# STM32F446_front_pane_-_northeast_-_v3.net
KiCad netlist of a schematic drawn in EAGLE
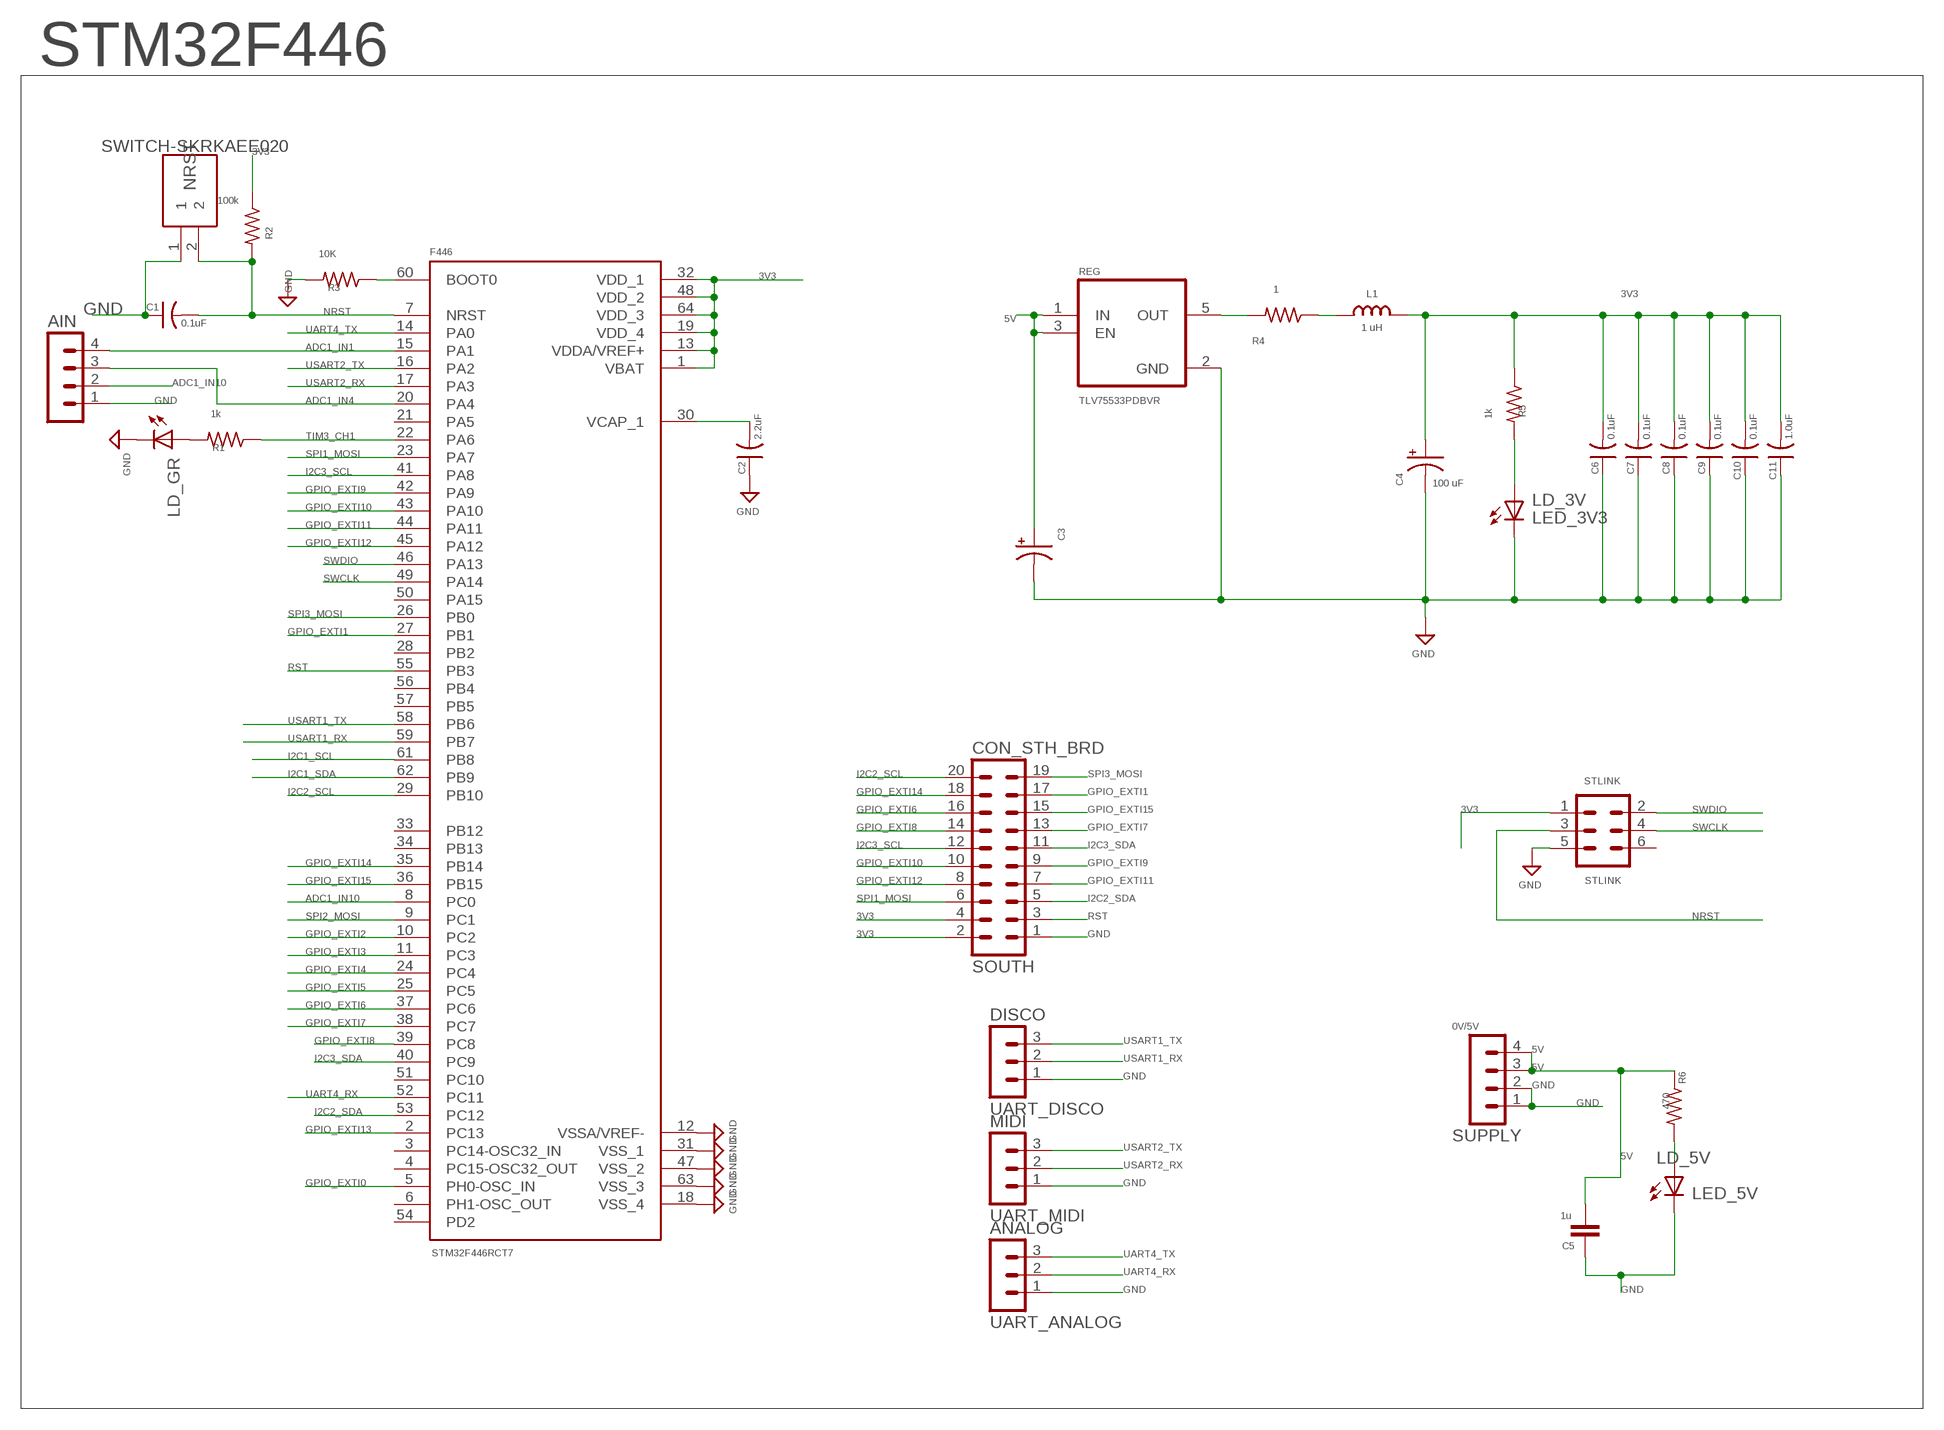
[diagram p0: schematic, sheet 1]
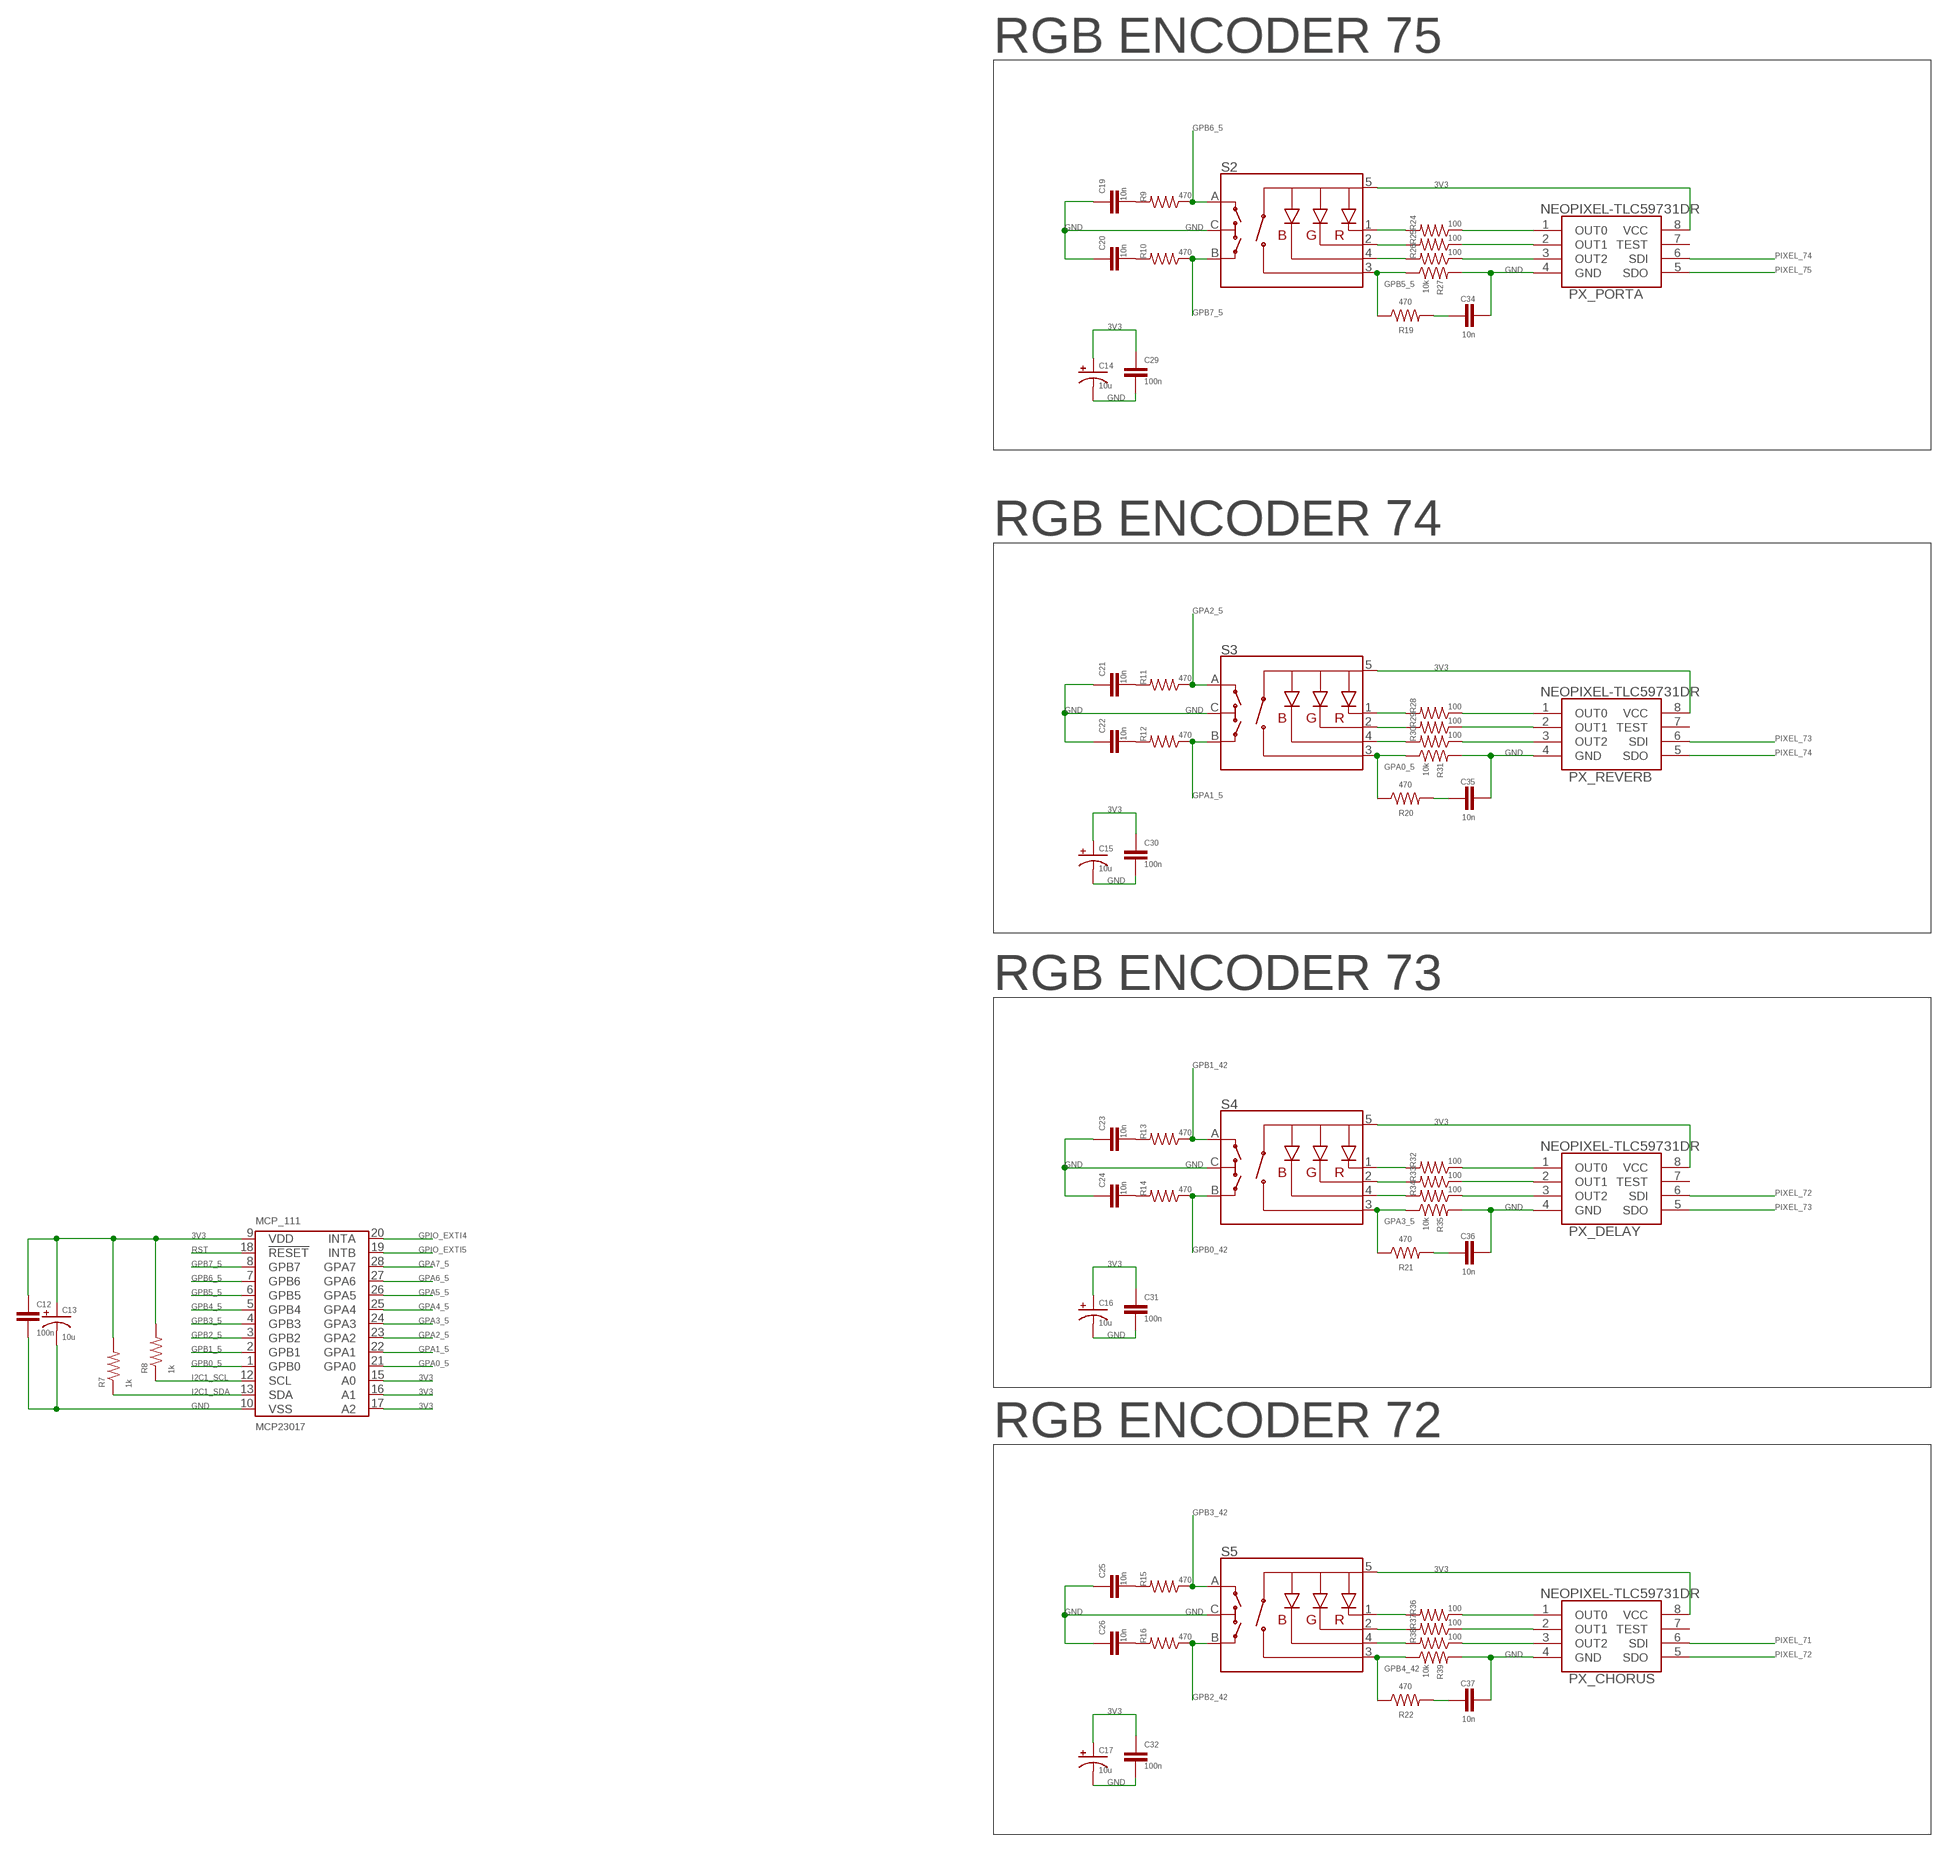
[diagram p1: schematic, sheet 2, part 1 of 2]
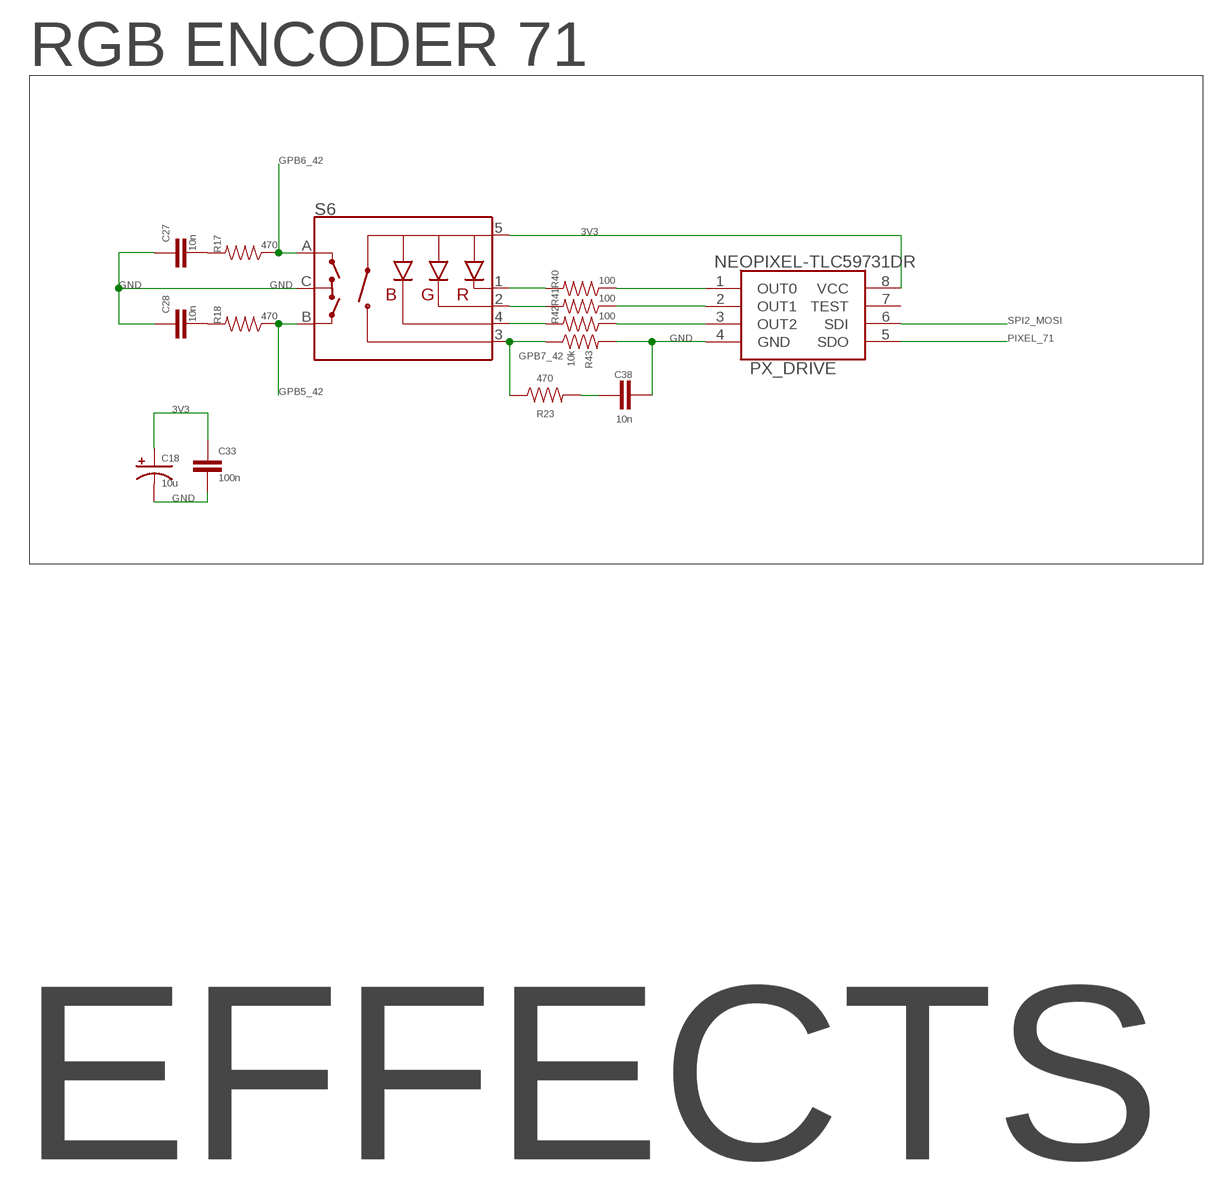
[diagram p2: schematic, sheet 2, part 2 of 2]
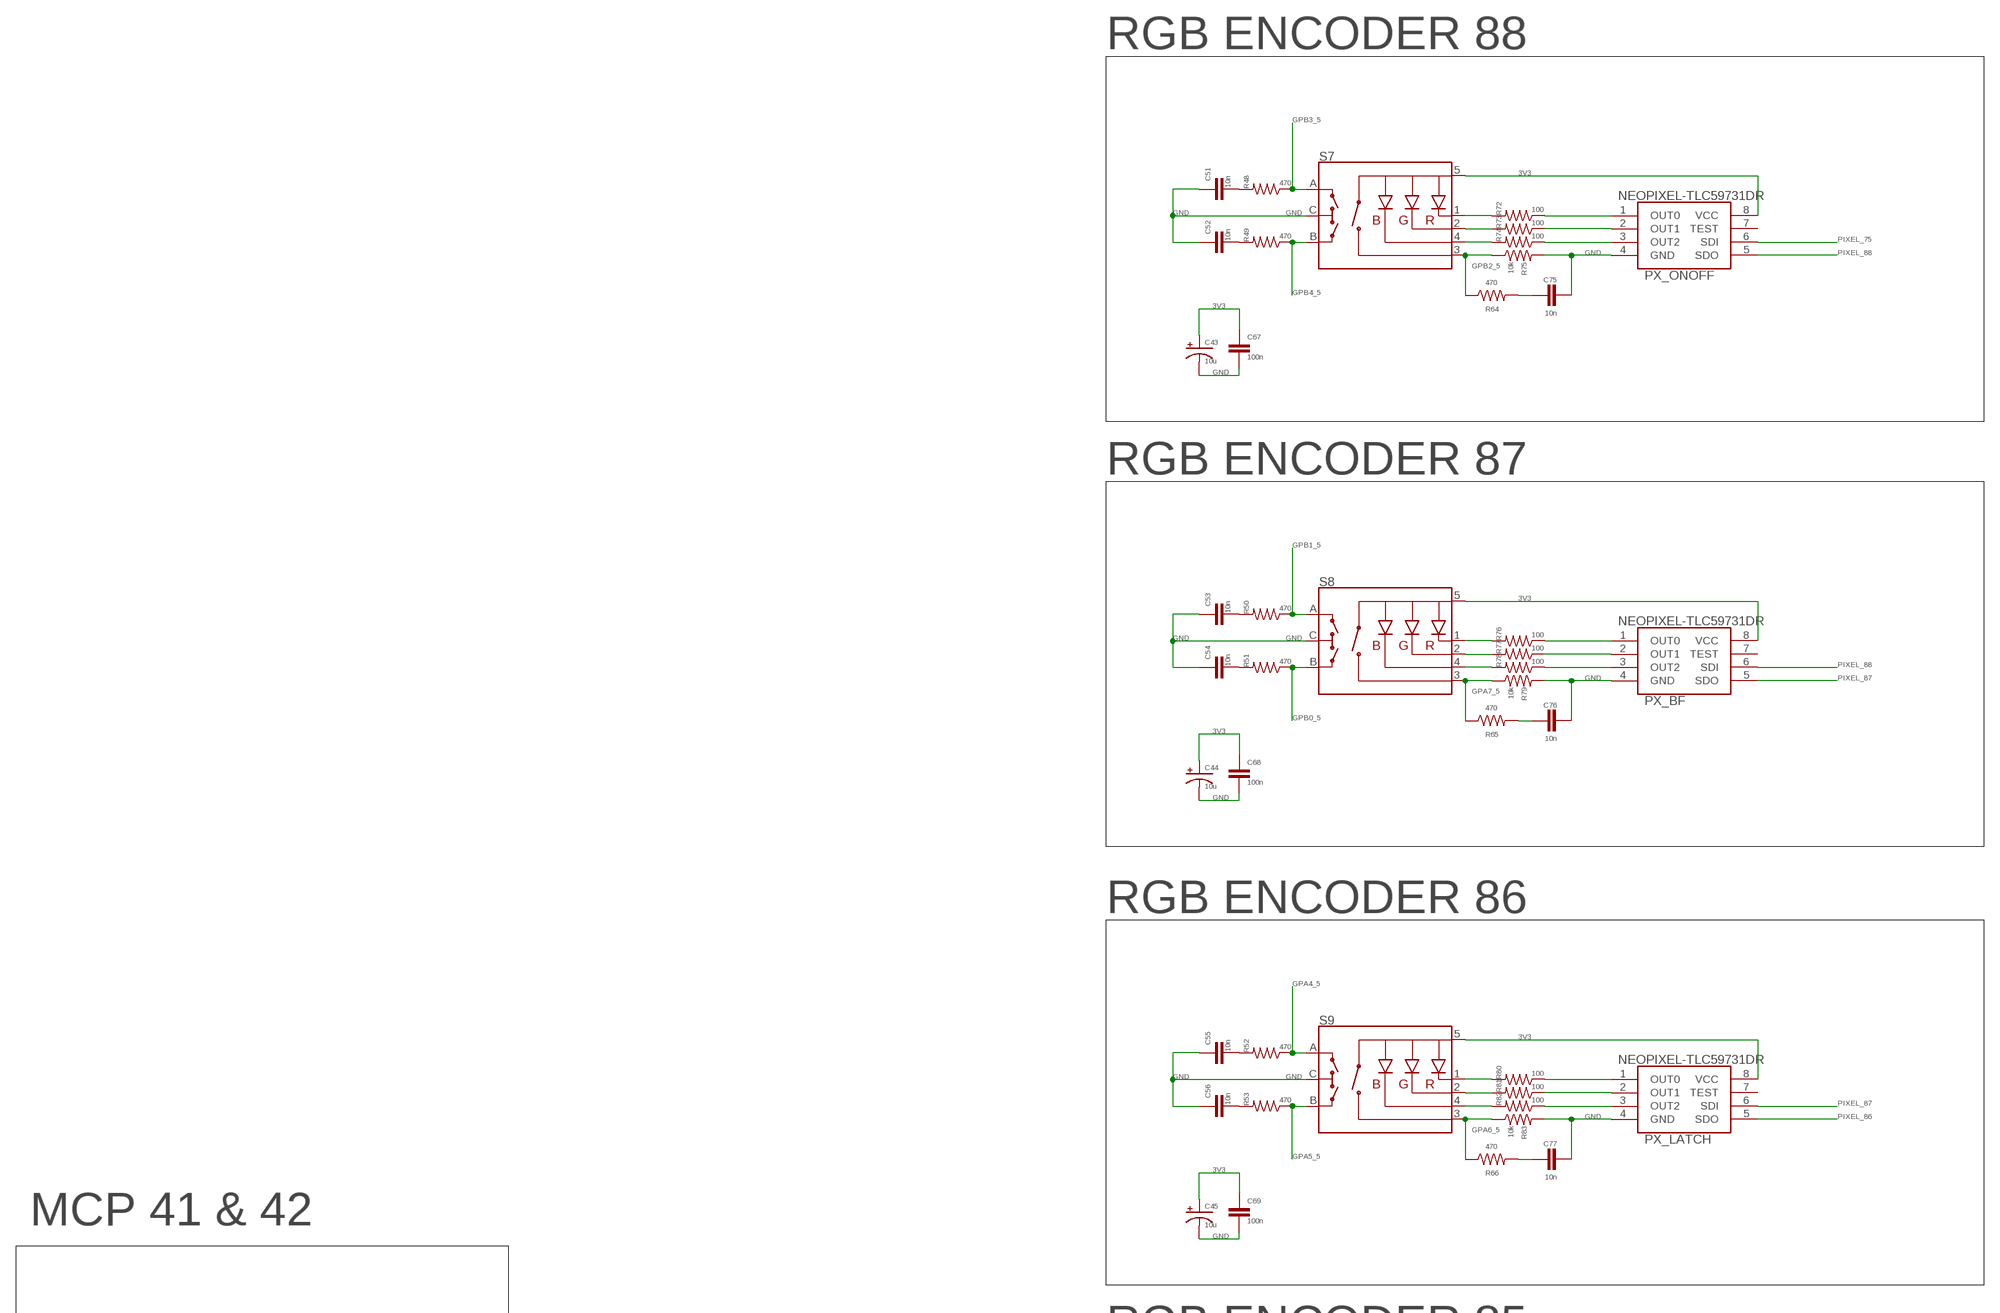
[diagram p3: schematic, sheet 3, part 1 of 2]
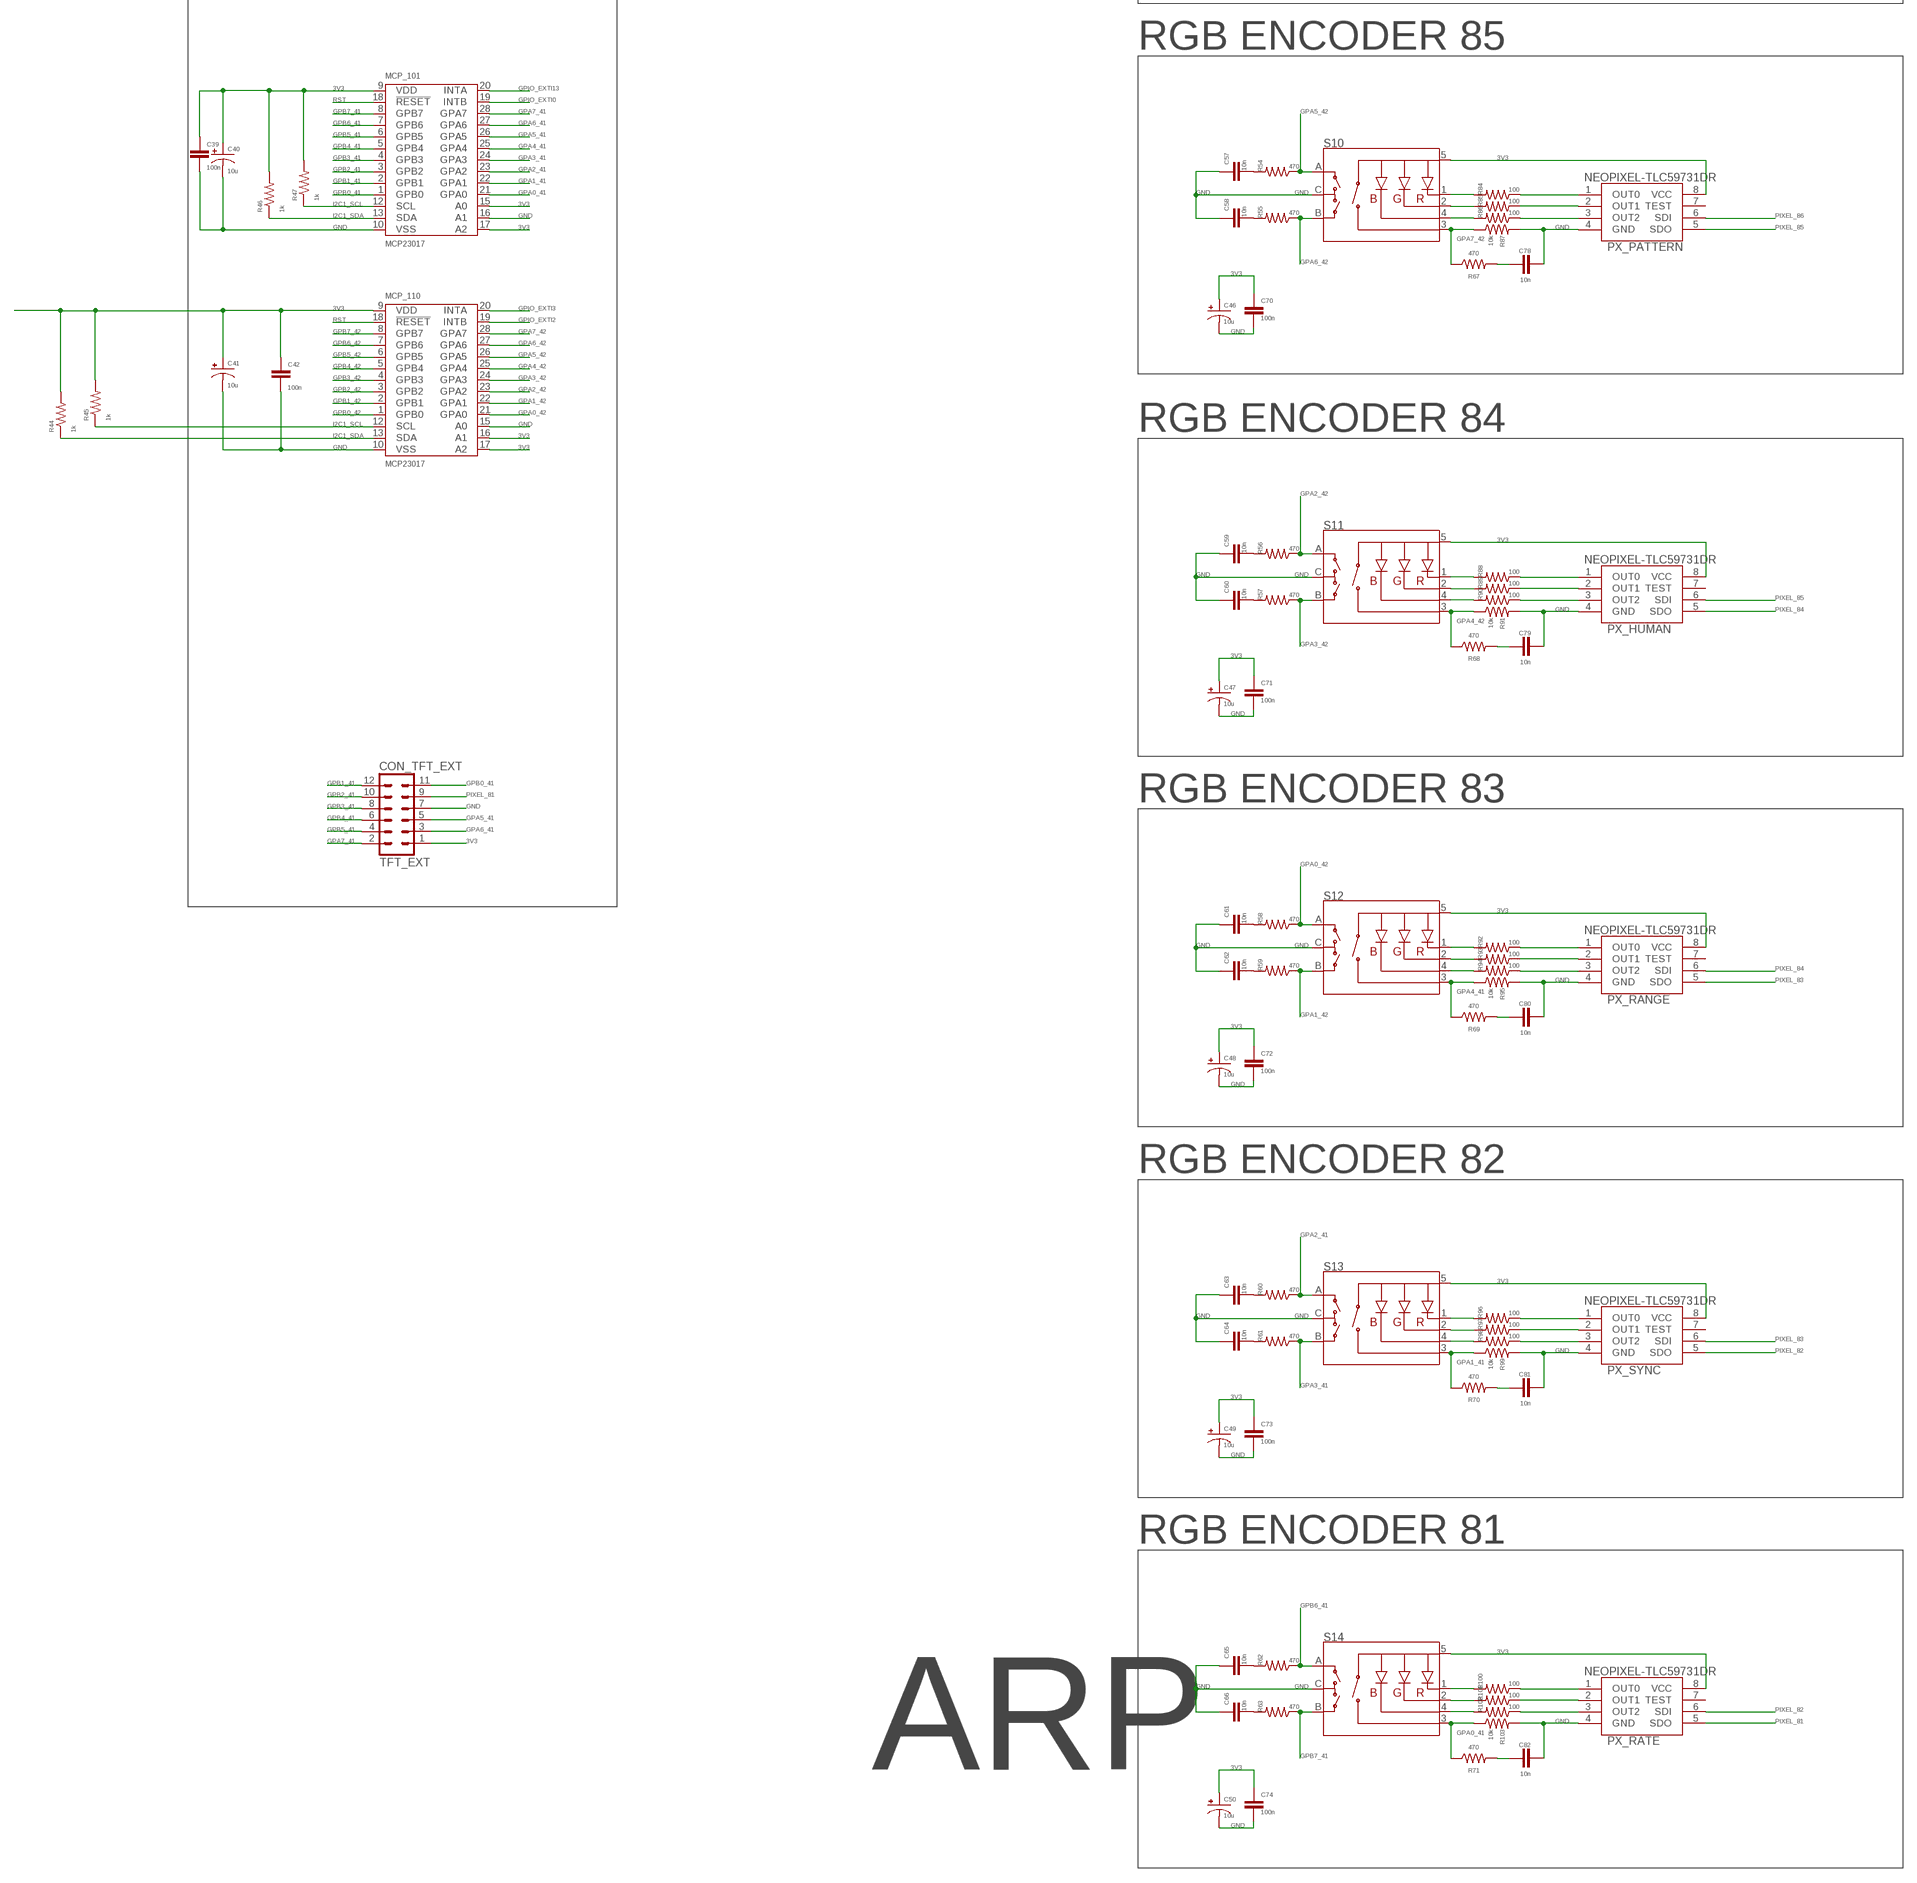
[diagram p4: schematic, sheet 3, part 2 of 2]

(export (version "E")
  (design (tool "Eeschema 10.0.6"))
  (components
    (comp (ref "C12")
      (value "100n")
      (footprint "eagle-import:0805-CAP")
      (libsource (lib "eagle-import") (part "PASSIF-CAP-0805"))
    )
    (comp (ref "C13")
      (value "10u")
      (footprint "eagle-import:CPOL2917")
      (libsource (lib "eagle-import") (part "PASSIF-CPOL-US2917"))
    )
    (comp (ref "C14")
      (value "10u")
      (footprint "eagle-import:CPOL2917")
      (libsource (lib "eagle-import") (part "PASSIF-CPOL-US2917"))
    )
    (comp (ref "C15")
      (value "10u")
      (footprint "eagle-import:CPOL2917")
      (libsource (lib "eagle-import") (part "PASSIF-CPOL-US2917"))
    )
    (comp (ref "C16")
      (value "10u")
      (footprint "eagle-import:CPOL2917")
      (libsource (lib "eagle-import") (part "PASSIF-CPOL-US2917"))
    )
    (comp (ref "C17")
      (value "10u")
      (footprint "eagle-import:CPOL2917")
      (libsource (lib "eagle-import") (part "PASSIF-CPOL-US2917"))
    )
    (comp (ref "C18")
      (value "10u")
      (footprint "eagle-import:CPOL2917")
      (libsource (lib "eagle-import") (part "PASSIF-CPOL-US2917"))
    )
    (comp (ref "C19")
      (value "10n")
      (footprint "eagle-import:0805-CAP")
      (libsource (lib "eagle-import") (part "PASSIF-CAP-0805"))
    )
    (comp (ref "C20")
      (value "10n")
      (footprint "eagle-import:0805-CAP")
      (libsource (lib "eagle-import") (part "PASSIF-CAP-0805"))
    )
    (comp (ref "C21")
      (value "10n")
      (footprint "eagle-import:0805-CAP")
      (libsource (lib "eagle-import") (part "PASSIF-CAP-0805"))
    )
    (comp (ref "C22")
      (value "10n")
      (footprint "eagle-import:0805-CAP")
      (libsource (lib "eagle-import") (part "PASSIF-CAP-0805"))
    )
    (comp (ref "C23")
      (value "10n")
      (footprint "eagle-import:0805-CAP")
      (libsource (lib "eagle-import") (part "PASSIF-CAP-0805"))
    )
    (comp (ref "C24")
      (value "10n")
      (footprint "eagle-import:0805-CAP")
      (libsource (lib "eagle-import") (part "PASSIF-CAP-0805"))
    )
    (comp (ref "C25")
      (value "10n")
      (footprint "eagle-import:0805-CAP")
      (libsource (lib "eagle-import") (part "PASSIF-CAP-0805"))
    )
    (comp (ref "C26")
      (value "10n")
      (footprint "eagle-import:0805-CAP")
      (libsource (lib "eagle-import") (part "PASSIF-CAP-0805"))
    )
    (comp (ref "C27")
      (value "10n")
      (footprint "eagle-import:0805-CAP")
      (libsource (lib "eagle-import") (part "PASSIF-CAP-0805"))
    )
    (comp (ref "C28")
      (value "10n")
      (footprint "eagle-import:0805-CAP")
      (libsource (lib "eagle-import") (part "PASSIF-CAP-0805"))
    )
    (comp (ref "C29")
      (value "100n")
      (footprint "eagle-import:0805-CAP")
      (libsource (lib "eagle-import") (part "PASSIF-CAP-0805"))
    )
    (comp (ref "C30")
      (value "100n")
      (footprint "eagle-import:0805-CAP")
      (libsource (lib "eagle-import") (part "PASSIF-CAP-0805"))
    )
    (comp (ref "C31")
      (value "100n")
      (footprint "eagle-import:0805-CAP")
      (libsource (lib "eagle-import") (part "PASSIF-CAP-0805"))
    )
    (comp (ref "C32")
      (value "100n")
      (footprint "eagle-import:0805-CAP")
      (libsource (lib "eagle-import") (part "PASSIF-CAP-0805"))
    )
    (comp (ref "C33")
      (value "100n")
      (footprint "eagle-import:0805-CAP")
      (libsource (lib "eagle-import") (part "PASSIF-CAP-0805"))
    )
    (comp (ref "C34")
      (value "10n")
      (footprint "eagle-import:0805-CAP")
      (libsource (lib "eagle-import") (part "PASSIF-CAP-0805"))
    )
    (comp (ref "C35")
      (value "10n")
      (footprint "eagle-import:0805-CAP")
      (libsource (lib "eagle-import") (part "PASSIF-CAP-0805"))
    )
    (comp (ref "C36")
      (value "10n")
      (footprint "eagle-import:0805-CAP")
      (libsource (lib "eagle-import") (part "PASSIF-CAP-0805"))
    )
    (comp (ref "C37")
      (value "10n")
      (footprint "eagle-import:0805-CAP")
      (libsource (lib "eagle-import") (part "PASSIF-CAP-0805"))
    )
    (comp (ref "C38")
      (value "10n")
      (footprint "eagle-import:0805-CAP")
      (libsource (lib "eagle-import") (part "PASSIF-CAP-0805"))
    )
    (comp (ref "MCP_111")
      (value "MCP23017")
      (footprint "eagle-import:SOIC-28")
      (libsource (lib "eagle-import") (part "MCP23017"))
    )
    (comp (ref "PX_CHORUS")
      (value "NEOPIXEL-TLC59731DR")
      (footprint "eagle-import:SOIC127P600X175-8N")
      (fields
        (field (name "ARROW_PART_NUMBER") "TLC59731DR")
        (field (name "MOUSER_PART_NUMBER") "595-TLC59731DR")
      )
      (libsource (lib "eagle-import") (part "NEOPIXEL-TLC59731DR"))
    )
    (comp (ref "PX_DELAY")
      (value "NEOPIXEL-TLC59731DR")
      (footprint "eagle-import:SOIC127P600X175-8N")
      (fields
        (field (name "ARROW_PART_NUMBER") "TLC59731DR")
        (field (name "MOUSER_PART_NUMBER") "595-TLC59731DR")
      )
      (libsource (lib "eagle-import") (part "NEOPIXEL-TLC59731DR"))
    )
    (comp (ref "PX_DRIVE")
      (value "NEOPIXEL-TLC59731DR")
      (footprint "eagle-import:SOIC127P600X175-8N")
      (fields
        (field (name "ARROW_PART_NUMBER") "TLC59731DR")
        (field (name "MOUSER_PART_NUMBER") "595-TLC59731DR")
      )
      (libsource (lib "eagle-import") (part "NEOPIXEL-TLC59731DR"))
    )
    (comp (ref "PX_PORTA")
      (value "NEOPIXEL-TLC59731DR")
      (footprint "eagle-import:SOIC127P600X175-8N")
      (fields
        (field (name "ARROW_PART_NUMBER") "TLC59731DR")
        (field (name "MOUSER_PART_NUMBER") "595-TLC59731DR")
      )
      (libsource (lib "eagle-import") (part "NEOPIXEL-TLC59731DR"))
    )
    (comp (ref "PX_REVERB")
      (value "NEOPIXEL-TLC59731DR")
      (footprint "eagle-import:SOIC127P600X175-8N")
      (fields
        (field (name "ARROW_PART_NUMBER") "TLC59731DR")
        (field (name "MOUSER_PART_NUMBER") "595-TLC59731DR")
      )
      (libsource (lib "eagle-import") (part "NEOPIXEL-TLC59731DR"))
    )
    (comp (ref "R7")
      (value "1k")
      (footprint "eagle-import:R0805")
      (libsource (lib "eagle-import") (part "R-US_R0805"))
    )
    (comp (ref "R8")
      (value "1k")
      (footprint "eagle-import:R0805")
      (libsource (lib "eagle-import") (part "R-US_R0805"))
    )
    (comp (ref "R9")
      (value "470")
      (footprint "eagle-import:1206")
      (libsource (lib "eagle-import") (part "PASSIF-RESISTOR-1206"))
    )
    (comp (ref "R10")
      (value "470")
      (footprint "eagle-import:1206")
      (libsource (lib "eagle-import") (part "PASSIF-RESISTOR-1206"))
    )
    (comp (ref "R11")
      (value "470")
      (footprint "eagle-import:1206")
      (libsource (lib "eagle-import") (part "PASSIF-RESISTOR-1206"))
    )
    (comp (ref "R12")
      (value "470")
      (footprint "eagle-import:1206")
      (libsource (lib "eagle-import") (part "PASSIF-RESISTOR-1206"))
    )
    (comp (ref "R13")
      (value "470")
      (footprint "eagle-import:1206")
      (libsource (lib "eagle-import") (part "PASSIF-RESISTOR-1206"))
    )
    (comp (ref "R14")
      (value "470")
      (footprint "eagle-import:1206")
      (libsource (lib "eagle-import") (part "PASSIF-RESISTOR-1206"))
    )
    (comp (ref "R15")
      (value "470")
      (footprint "eagle-import:1206")
      (libsource (lib "eagle-import") (part "PASSIF-RESISTOR-1206"))
    )
    (comp (ref "R16")
      (value "470")
      (footprint "eagle-import:1206")
      (libsource (lib "eagle-import") (part "PASSIF-RESISTOR-1206"))
    )
    (comp (ref "R17")
      (value "470")
      (footprint "eagle-import:1206")
      (libsource (lib "eagle-import") (part "PASSIF-RESISTOR-1206"))
    )
    (comp (ref "R18")
      (value "470")
      (footprint "eagle-import:1206")
      (libsource (lib "eagle-import") (part "PASSIF-RESISTOR-1206"))
    )
    (comp (ref "R19")
      (value "470")
      (footprint "eagle-import:1206")
      (libsource (lib "eagle-import") (part "PASSIF-RESISTOR-1206"))
    )
    (comp (ref "R20")
      (value "470")
      (footprint "eagle-import:1206")
      (libsource (lib "eagle-import") (part "PASSIF-RESISTOR-1206"))
    )
    (comp (ref "R21")
      (value "470")
      (footprint "eagle-import:1206")
      (libsource (lib "eagle-import") (part "PASSIF-RESISTOR-1206"))
    )
    (comp (ref "R22")
      (value "470")
      (footprint "eagle-import:1206")
      (libsource (lib "eagle-import") (part "PASSIF-RESISTOR-1206"))
    )
    (comp (ref "R23")
      (value "470")
      (footprint "eagle-import:1206")
      (libsource (lib "eagle-import") (part "PASSIF-RESISTOR-1206"))
    )
    (comp (ref "R24")
      (value "100")
      (footprint "eagle-import:1206")
      (libsource (lib "eagle-import") (part "PASSIF-RESISTOR-1206"))
    )
    (comp (ref "R25")
      (value "100")
      (footprint "eagle-import:1206")
      (libsource (lib "eagle-import") (part "PASSIF-RESISTOR-1206"))
    )
    (comp (ref "R26")
      (value "100")
      (footprint "eagle-import:1206")
      (libsource (lib "eagle-import") (part "PASSIF-RESISTOR-1206"))
    )
    (comp (ref "R27")
      (value "10k")
      (footprint "eagle-import:1206")
      (libsource (lib "eagle-import") (part "PASSIF-RESISTOR-1206"))
    )
    (comp (ref "R28")
      (value "100")
      (footprint "eagle-import:1206")
      (libsource (lib "eagle-import") (part "PASSIF-RESISTOR-1206"))
    )
    (comp (ref "R29")
      (value "100")
      (footprint "eagle-import:1206")
      (libsource (lib "eagle-import") (part "PASSIF-RESISTOR-1206"))
    )
    (comp (ref "R30")
      (value "100")
      (footprint "eagle-import:1206")
      (libsource (lib "eagle-import") (part "PASSIF-RESISTOR-1206"))
    )
    (comp (ref "R31")
      (value "10k")
      (footprint "eagle-import:1206")
      (libsource (lib "eagle-import") (part "PASSIF-RESISTOR-1206"))
    )
    (comp (ref "R32")
      (value "100")
      (footprint "eagle-import:1206")
      (libsource (lib "eagle-import") (part "PASSIF-RESISTOR-1206"))
    )
    (comp (ref "R33")
      (value "100")
      (footprint "eagle-import:1206")
      (libsource (lib "eagle-import") (part "PASSIF-RESISTOR-1206"))
    )
    (comp (ref "R34")
      (value "100")
      (footprint "eagle-import:1206")
      (libsource (lib "eagle-import") (part "PASSIF-RESISTOR-1206"))
    )
    (comp (ref "R35")
      (value "10k")
      (footprint "eagle-import:1206")
      (libsource (lib "eagle-import") (part "PASSIF-RESISTOR-1206"))
    )
    (comp (ref "R36")
      (value "100")
      (footprint "eagle-import:1206")
      (libsource (lib "eagle-import") (part "PASSIF-RESISTOR-1206"))
    )
    (comp (ref "R37")
      (value "100")
      (footprint "eagle-import:1206")
      (libsource (lib "eagle-import") (part "PASSIF-RESISTOR-1206"))
    )
    (comp (ref "R38")
      (value "100")
      (footprint "eagle-import:1206")
      (libsource (lib "eagle-import") (part "PASSIF-RESISTOR-1206"))
    )
    (comp (ref "R39")
      (value "10k")
      (footprint "eagle-import:1206")
      (libsource (lib "eagle-import") (part "PASSIF-RESISTOR-1206"))
    )
    (comp (ref "R40")
      (value "100")
      (footprint "eagle-import:1206")
      (libsource (lib "eagle-import") (part "PASSIF-RESISTOR-1206"))
    )
    (comp (ref "R41")
      (value "100")
      (footprint "eagle-import:1206")
      (libsource (lib "eagle-import") (part "PASSIF-RESISTOR-1206"))
    )
    (comp (ref "R42")
      (value "100")
      (footprint "eagle-import:1206")
      (libsource (lib "eagle-import") (part "PASSIF-RESISTOR-1206"))
    )
    (comp (ref "R43")
      (value "10k")
      (footprint "eagle-import:1206")
      (libsource (lib "eagle-import") (part "PASSIF-RESISTOR-1206"))
    )
    (comp (ref "S2")
      (value "ENCODER-RGB-SWITCH-NO_NUT")
      (footprint "eagle-import:ENCODER_LED_3")
      (libsource (lib "eagle-import") (part "ENCODER-RGB-SWITCH-NO_NUT"))
    )
    (comp (ref "S3")
      (value "ENCODER-RGB-SWITCH-NO_NUT")
      (footprint "eagle-import:ENCODER_LED_3")
      (libsource (lib "eagle-import") (part "ENCODER-RGB-SWITCH-NO_NUT"))
    )
    (comp (ref "S4")
      (value "ENCODER-RGB-SWITCH-NO_NUT")
      (footprint "eagle-import:ENCODER_LED_3")
      (libsource (lib "eagle-import") (part "ENCODER-RGB-SWITCH-NO_NUT"))
    )
    (comp (ref "S5")
      (value "ENCODER-RGB-SWITCH-NO_NUT")
      (footprint "eagle-import:ENCODER_LED_3")
      (libsource (lib "eagle-import") (part "ENCODER-RGB-SWITCH-NO_NUT"))
    )
    (comp (ref "S6")
      (value "ENCODER-RGB-SWITCH-NO_NUT")
      (footprint "eagle-import:ENCODER_LED_3")
      (libsource (lib "eagle-import") (part "ENCODER-RGB-SWITCH-NO_NUT"))
    )
    (comp (ref "0V/5V")
      (value "SUPPLY")
      (footprint "eagle-import:MA04-1")
      (libsource (lib "eagle-import") (part "PINHEADER-M04PL"))
    )
    (comp (ref "AIN")
      (value "MA04-1")
      (footprint "eagle-import:MA04-1")
      (libsource (lib "eagle-import") (part "MA04-1"))
    )
    (comp (ref "ANALOG")
      (value "UART_ANALOG")
      (footprint "eagle-import:MA03-1")
      (libsource (lib "eagle-import") (part "MA03-1"))
    )
    (comp (ref "C1")
      (value "0.1uF")
      (footprint "eagle-import:C0805")
      (libsource (lib "eagle-import") (part "C-US0805"))
    )
    (comp (ref "C2")
      (value "2.2uF")
      (footprint "eagle-import:C0805")
      (libsource (lib "eagle-import") (part "C-US0805"))
    )
    (comp (ref "C3")
      (value "10u")
      (footprint "eagle-import:CPOL2917")
      (libsource (lib "eagle-import") (part "CPOL-US2917"))
    )
    (comp (ref "C4")
      (value "100 uF")
      (footprint "eagle-import:CPOL2917")
      (libsource (lib "eagle-import") (part "CPOL-US2917"))
    )
    (comp (ref "C5")
      (value "1u")
      (footprint "eagle-import:C1206")
      (libsource (lib "eagle-import") (part "C-EUC1206"))
    )
    (comp (ref "C6")
      (value "0.1uF")
      (footprint "eagle-import:C0805")
      (libsource (lib "eagle-import") (part "C-US0805"))
    )
    (comp (ref "C7")
      (value "0.1uF")
      (footprint "eagle-import:C0805")
      (libsource (lib "eagle-import") (part "C-US0805"))
    )
    (comp (ref "C8")
      (value "0.1uF")
      (footprint "eagle-import:C0805")
      (libsource (lib "eagle-import") (part "C-US0805"))
    )
    (comp (ref "C9")
      (value "0.1uF")
      (footprint "eagle-import:C0805")
      (libsource (lib "eagle-import") (part "C-US0805"))
    )
    (comp (ref "C10")
      (value "0.1uF")
      (footprint "eagle-import:C0805")
      (libsource (lib "eagle-import") (part "C-US0805"))
    )
    (comp (ref "C11")
      (value "1.0uF")
      (footprint "eagle-import:C0805")
      (libsource (lib "eagle-import") (part "C-US0805"))
    )
    (comp (ref "CON_STH_BRD")
      (value "SOUTH")
      (footprint "eagle-import:MA10-2")
      (libsource (lib "eagle-import") (part "MA10-2"))
    )
    (comp (ref "DISCO")
      (value "UART_DISCO")
      (footprint "eagle-import:MA03-1")
      (libsource (lib "eagle-import") (part "MA03-1"))
    )
    (comp (ref "F446")
      (value "STM32F446RCT7")
      (footprint "eagle-import:QFP50P1200X1200X160-64N")
      (fields (field (name "MF") "STMicroelectronics"))
      (libsource (lib "eagle-import") (part "STM32F446RCT7"))
    )
    (comp (ref "L1")
      (value "1 uH")
      (footprint "eagle-import:L0805")
      (libsource (lib "eagle-import") (part "L-USL0805"))
    )
    (comp (ref "LD_3V")
      (value "LED_3V3")
      (footprint "eagle-import:0805-LED")
      (libsource (lib "eagle-import") (part "LED-0805"))
    )
    (comp (ref "LD_5V")
      (value "LED_5V")
      (footprint "eagle-import:0603-LED")
      (libsource (lib "eagle-import") (part "LED-0603"))
    )
    (comp (ref "LD_GR")
      (value "LED-0805")
      (footprint "eagle-import:0805-LED")
      (libsource (lib "eagle-import") (part "LED-0805"))
    )
    (comp (ref "MIDI")
      (value "UART_MIDI")
      (footprint "eagle-import:MA03-1")
      (libsource (lib "eagle-import") (part "MA03-1"))
    )
    (comp (ref "NRST")
      (value "SWITCH-SKRKAEE020")
      (footprint "eagle-import:SKRKAEE020")
      (fields
        (field (name "MANUFACTURER_PART_NUMBER") "SKRKAEE020")
        (field (name "MOUSER_PART_NUMBER") "688-SKRKAEE020")
      )
      (libsource (lib "eagle-import") (part "SWITCH-SKRKAEE020"))
    )
    (comp (ref "R1")
      (value "1k")
      (footprint "eagle-import:R0805")
      (libsource (lib "eagle-import") (part "R-US0805"))
    )
    (comp (ref "R2")
      (value "100k")
      (footprint "eagle-import:R0805")
      (libsource (lib "eagle-import") (part "R-US0805"))
    )
    (comp (ref "R3")
      (value "10K")
      (footprint "eagle-import:R0805")
      (libsource (lib "eagle-import") (part "R-US0805"))
    )
    (comp (ref "R4")
      (value "1")
      (footprint "eagle-import:R0805")
      (libsource (lib "eagle-import") (part "R-US0805"))
    )
    (comp (ref "R5")
      (value "1k")
      (footprint "eagle-import:R0805")
      (libsource (lib "eagle-import") (part "R-US0805"))
    )
    (comp (ref "R6")
      (value "470")
      (footprint "eagle-import:R0805")
      (libsource (lib "eagle-import") (part "R-US0805"))
    )
    (comp (ref "REG")
      (value "TLV75533PDBVR")
      (footprint "eagle-import:SOT95P280X145-5N")
      (fields (field (name "MF") "Texas Instruments"))
      (libsource (lib "eagle-import") (part "TLV75533PDBVR"))
    )
    (comp (ref "STLINK")
      (value "STLINK")
      (footprint "eagle-import:MA03-2")
      (libsource (lib "eagle-import") (part "MA03-2"))
    )
    (comp (ref "C39")
      (value "100n")
      (footprint "eagle-import:0805-CAP")
      (libsource (lib "eagle-import") (part "PASSIF-CAP-0805"))
    )
    (comp (ref "C40")
      (value "10u")
      (footprint "eagle-import:CPOL2917")
      (libsource (lib "eagle-import") (part "PASSIF-CPOL-US2917"))
    )
    (comp (ref "C41")
      (value "10u")
      (footprint "eagle-import:CPOL2917")
      (libsource (lib "eagle-import") (part "PASSIF-CPOL-US2917"))
    )
    (comp (ref "C42")
      (value "100n")
      (footprint "eagle-import:0805-CAP")
      (libsource (lib "eagle-import") (part "PASSIF-CAP-0805"))
    )
    (comp (ref "C43")
      (value "10u")
      (footprint "eagle-import:CPOL2917")
      (libsource (lib "eagle-import") (part "PASSIF-CPOL-US2917"))
    )
    (comp (ref "C44")
      (value "10u")
      (footprint "eagle-import:CPOL2917")
      (libsource (lib "eagle-import") (part "PASSIF-CPOL-US2917"))
    )
    (comp (ref "C45")
      (value "10u")
      (footprint "eagle-import:CPOL2917")
      (libsource (lib "eagle-import") (part "PASSIF-CPOL-US2917"))
    )
    (comp (ref "C46")
      (value "10u")
      (footprint "eagle-import:CPOL2917")
      (libsource (lib "eagle-import") (part "PASSIF-CPOL-US2917"))
    )
    (comp (ref "C47")
      (value "10u")
      (footprint "eagle-import:CPOL2917")
      (libsource (lib "eagle-import") (part "PASSIF-CPOL-US2917"))
    )
    (comp (ref "C48")
      (value "10u")
      (footprint "eagle-import:CPOL2917")
      (libsource (lib "eagle-import") (part "PASSIF-CPOL-US2917"))
    )
    (comp (ref "C49")
      (value "10u")
      (footprint "eagle-import:CPOL2917")
      (libsource (lib "eagle-import") (part "PASSIF-CPOL-US2917"))
    )
    (comp (ref "C50")
      (value "10u")
      (footprint "eagle-import:CPOL2917")
      (libsource (lib "eagle-import") (part "PASSIF-CPOL-US2917"))
    )
    (comp (ref "C51")
      (value "10n")
      (footprint "eagle-import:0805-CAP")
      (libsource (lib "eagle-import") (part "PASSIF-CAP-0805"))
    )
    (comp (ref "C52")
      (value "10n")
      (footprint "eagle-import:0805-CAP")
      (libsource (lib "eagle-import") (part "PASSIF-CAP-0805"))
    )
    (comp (ref "C53")
      (value "10n")
      (footprint "eagle-import:0805-CAP")
      (libsource (lib "eagle-import") (part "PASSIF-CAP-0805"))
    )
    (comp (ref "C54")
      (value "10n")
      (footprint "eagle-import:0805-CAP")
      (libsource (lib "eagle-import") (part "PASSIF-CAP-0805"))
    )
    (comp (ref "C55")
      (value "10n")
      (footprint "eagle-import:0805-CAP")
      (libsource (lib "eagle-import") (part "PASSIF-CAP-0805"))
    )
    (comp (ref "C56")
      (value "10n")
      (footprint "eagle-import:0805-CAP")
      (libsource (lib "eagle-import") (part "PASSIF-CAP-0805"))
    )
    (comp (ref "C57")
      (value "10n")
      (footprint "eagle-import:0805-CAP")
      (libsource (lib "eagle-import") (part "PASSIF-CAP-0805"))
    )
    (comp (ref "C58")
      (value "10n")
      (footprint "eagle-import:0805-CAP")
      (libsource (lib "eagle-import") (part "PASSIF-CAP-0805"))
    )
    (comp (ref "C59")
      (value "10n")
      (footprint "eagle-import:0805-CAP")
      (libsource (lib "eagle-import") (part "PASSIF-CAP-0805"))
    )
    (comp (ref "C60")
      (value "10n")
      (footprint "eagle-import:0805-CAP")
      (libsource (lib "eagle-import") (part "PASSIF-CAP-0805"))
    )
    (comp (ref "C61")
      (value "10n")
      (footprint "eagle-import:0805-CAP")
      (libsource (lib "eagle-import") (part "PASSIF-CAP-0805"))
    )
    (comp (ref "C62")
      (value "10n")
      (footprint "eagle-import:0805-CAP")
      (libsource (lib "eagle-import") (part "PASSIF-CAP-0805"))
    )
    (comp (ref "C63")
      (value "10n")
      (footprint "eagle-import:0805-CAP")
      (libsource (lib "eagle-import") (part "PASSIF-CAP-0805"))
    )
    (comp (ref "C64")
      (value "10n")
      (footprint "eagle-import:0805-CAP")
      (libsource (lib "eagle-import") (part "PASSIF-CAP-0805"))
    )
    (comp (ref "C65")
      (value "10n")
      (footprint "eagle-import:0805-CAP")
      (libsource (lib "eagle-import") (part "PASSIF-CAP-0805"))
    )
    (comp (ref "C66")
      (value "10n")
      (footprint "eagle-import:0805-CAP")
      (libsource (lib "eagle-import") (part "PASSIF-CAP-0805"))
    )
    (comp (ref "C67")
      (value "100n")
      (footprint "eagle-import:0805-CAP")
      (libsource (lib "eagle-import") (part "PASSIF-CAP-0805"))
    )
    (comp (ref "C68")
      (value "100n")
      (footprint "eagle-import:0805-CAP")
      (libsource (lib "eagle-import") (part "PASSIF-CAP-0805"))
    )
    (comp (ref "C69")
      (value "100n")
      (footprint "eagle-import:0805-CAP")
      (libsource (lib "eagle-import") (part "PASSIF-CAP-0805"))
    )
    (comp (ref "C70")
      (value "100n")
      (footprint "eagle-import:0805-CAP")
      (libsource (lib "eagle-import") (part "PASSIF-CAP-0805"))
    )
    (comp (ref "C71")
      (value "100n")
      (footprint "eagle-import:0805-CAP")
      (libsource (lib "eagle-import") (part "PASSIF-CAP-0805"))
    )
    (comp (ref "C72")
      (value "100n")
      (footprint "eagle-import:0805-CAP")
      (libsource (lib "eagle-import") (part "PASSIF-CAP-0805"))
    )
    (comp (ref "C73")
      (value "100n")
      (footprint "eagle-import:0805-CAP")
      (libsource (lib "eagle-import") (part "PASSIF-CAP-0805"))
    )
    (comp (ref "C74")
      (value "100n")
      (footprint "eagle-import:0805-CAP")
      (libsource (lib "eagle-import") (part "PASSIF-CAP-0805"))
    )
    (comp (ref "C75")
      (value "10n")
      (footprint "eagle-import:0805-CAP")
      (libsource (lib "eagle-import") (part "PASSIF-CAP-0805"))
    )
    (comp (ref "C76")
      (value "10n")
      (footprint "eagle-import:0805-CAP")
      (libsource (lib "eagle-import") (part "PASSIF-CAP-0805"))
    )
    (comp (ref "C77")
      (value "10n")
      (footprint "eagle-import:0805-CAP")
      (libsource (lib "eagle-import") (part "PASSIF-CAP-0805"))
    )
    (comp (ref "C78")
      (value "10n")
      (footprint "eagle-import:0805-CAP")
      (libsource (lib "eagle-import") (part "PASSIF-CAP-0805"))
    )
    (comp (ref "C79")
      (value "10n")
      (footprint "eagle-import:0805-CAP")
      (libsource (lib "eagle-import") (part "PASSIF-CAP-0805"))
    )
    (comp (ref "C80")
      (value "10n")
      (footprint "eagle-import:0805-CAP")
      (libsource (lib "eagle-import") (part "PASSIF-CAP-0805"))
    )
    (comp (ref "C81")
      (value "10n")
      (footprint "eagle-import:0805-CAP")
      (libsource (lib "eagle-import") (part "PASSIF-CAP-0805"))
    )
    (comp (ref "C82")
      (value "10n")
      (footprint "eagle-import:0805-CAP")
      (libsource (lib "eagle-import") (part "PASSIF-CAP-0805"))
    )
    (comp (ref "CON_TFT_EXT")
      (value "TFT_EXT")
      (footprint "eagle-import:MA06-2")
      (libsource (lib "eagle-import") (part "MA06-2"))
    )
    (comp (ref "MCP_101")
      (value "MCP23017")
      (footprint "eagle-import:SOIC-28")
      (libsource (lib "eagle-import") (part "MCP23017"))
    )
    (comp (ref "MCP_110")
      (value "MCP23017")
      (footprint "eagle-import:SOIC-28")
      (libsource (lib "eagle-import") (part "MCP23017"))
    )
    (comp (ref "PX_BF")
      (value "NEOPIXEL-TLC59731DR")
      (footprint "eagle-import:SOIC127P600X175-8N")
      (fields
        (field (name "ARROW_PART_NUMBER") "TLC59731DR")
        (field (name "MOUSER_PART_NUMBER") "595-TLC59731DR")
      )
      (libsource (lib "eagle-import") (part "NEOPIXEL-TLC59731DR"))
    )
    (comp (ref "PX_HUMAN")
      (value "NEOPIXEL-TLC59731DR")
      (footprint "eagle-import:SOIC127P600X175-8N")
      (fields
        (field (name "ARROW_PART_NUMBER") "TLC59731DR")
        (field (name "MOUSER_PART_NUMBER") "595-TLC59731DR")
      )
      (libsource (lib "eagle-import") (part "NEOPIXEL-TLC59731DR"))
    )
    (comp (ref "PX_LATCH")
      (value "NEOPIXEL-TLC59731DR")
      (footprint "eagle-import:SOIC127P600X175-8N")
      (fields
        (field (name "ARROW_PART_NUMBER") "TLC59731DR")
        (field (name "MOUSER_PART_NUMBER") "595-TLC59731DR")
      )
      (libsource (lib "eagle-import") (part "NEOPIXEL-TLC59731DR"))
    )
    (comp (ref "PX_ONOFF")
      (value "NEOPIXEL-TLC59731DR")
      (footprint "eagle-import:SOIC127P600X175-8N")
      (fields
        (field (name "ARROW_PART_NUMBER") "TLC59731DR")
        (field (name "MOUSER_PART_NUMBER") "595-TLC59731DR")
      )
      (libsource (lib "eagle-import") (part "NEOPIXEL-TLC59731DR"))
    )
    (comp (ref "PX_PATTERN")
      (value "NEOPIXEL-TLC59731DR")
      (footprint "eagle-import:SOIC127P600X175-8N")
      (fields
        (field (name "ARROW_PART_NUMBER") "TLC59731DR")
        (field (name "MOUSER_PART_NUMBER") "595-TLC59731DR")
      )
      (libsource (lib "eagle-import") (part "NEOPIXEL-TLC59731DR"))
    )
    (comp (ref "PX_RANGE")
      (value "NEOPIXEL-TLC59731DR")
      (footprint "eagle-import:SOIC127P600X175-8N")
      (fields
        (field (name "ARROW_PART_NUMBER") "TLC59731DR")
        (field (name "MOUSER_PART_NUMBER") "595-TLC59731DR")
      )
      (libsource (lib "eagle-import") (part "NEOPIXEL-TLC59731DR"))
    )
    (comp (ref "PX_RATE")
      (value "NEOPIXEL-TLC59731DR")
      (footprint "eagle-import:SOIC127P600X175-8N")
      (fields
        (field (name "ARROW_PART_NUMBER") "TLC59731DR")
        (field (name "MOUSER_PART_NUMBER") "595-TLC59731DR")
      )
      (libsource (lib "eagle-import") (part "NEOPIXEL-TLC59731DR"))
    )
    (comp (ref "PX_SYNC")
      (value "NEOPIXEL-TLC59731DR")
      (footprint "eagle-import:SOIC127P600X175-8N")
      (fields
        (field (name "ARROW_PART_NUMBER") "TLC59731DR")
        (field (name "MOUSER_PART_NUMBER") "595-TLC59731DR")
      )
      (libsource (lib "eagle-import") (part "NEOPIXEL-TLC59731DR"))
    )
    (comp (ref "R44")
      (value "1k")
      (footprint "eagle-import:R0805")
      (libsource (lib "eagle-import") (part "R-US_R0805"))
    )
    (comp (ref "R45")
      (value "1k")
      (footprint "eagle-import:R0805")
      (libsource (lib "eagle-import") (part "R-US_R0805"))
    )
    (comp (ref "R46")
      (value "1k")
      (footprint "eagle-import:R0805")
      (libsource (lib "eagle-import") (part "R-US_R0805"))
    )
    (comp (ref "R47")
      (value "1k")
      (footprint "eagle-import:R0805")
      (libsource (lib "eagle-import") (part "R-US_R0805"))
    )
    (comp (ref "R48")
      (value "470")
      (footprint "eagle-import:1206")
      (libsource (lib "eagle-import") (part "PASSIF-RESISTOR-1206"))
    )
    (comp (ref "R49")
      (value "470")
      (footprint "eagle-import:1206")
      (libsource (lib "eagle-import") (part "PASSIF-RESISTOR-1206"))
    )
    (comp (ref "R50")
      (value "470")
      (footprint "eagle-import:1206")
      (libsource (lib "eagle-import") (part "PASSIF-RESISTOR-1206"))
    )
    (comp (ref "R51")
      (value "470")
      (footprint "eagle-import:1206")
      (libsource (lib "eagle-import") (part "PASSIF-RESISTOR-1206"))
    )
    (comp (ref "R52")
      (value "470")
      (footprint "eagle-import:1206")
      (libsource (lib "eagle-import") (part "PASSIF-RESISTOR-1206"))
    )
    (comp (ref "R53")
      (value "470")
      (footprint "eagle-import:1206")
      (libsource (lib "eagle-import") (part "PASSIF-RESISTOR-1206"))
    )
    (comp (ref "R54")
      (value "470")
      (footprint "eagle-import:1206")
      (libsource (lib "eagle-import") (part "PASSIF-RESISTOR-1206"))
    )
    (comp (ref "R55")
      (value "470")
      (footprint "eagle-import:1206")
      (libsource (lib "eagle-import") (part "PASSIF-RESISTOR-1206"))
    )
    (comp (ref "R56")
      (value "470")
      (footprint "eagle-import:1206")
      (libsource (lib "eagle-import") (part "PASSIF-RESISTOR-1206"))
    )
    (comp (ref "R57")
      (value "470")
      (footprint "eagle-import:1206")
      (libsource (lib "eagle-import") (part "PASSIF-RESISTOR-1206"))
    )
    (comp (ref "R58")
      (value "470")
      (footprint "eagle-import:1206")
      (libsource (lib "eagle-import") (part "PASSIF-RESISTOR-1206"))
    )
    (comp (ref "R59")
      (value "470")
      (footprint "eagle-import:1206")
      (libsource (lib "eagle-import") (part "PASSIF-RESISTOR-1206"))
    )
    (comp (ref "R60")
      (value "470")
      (footprint "eagle-import:1206")
      (libsource (lib "eagle-import") (part "PASSIF-RESISTOR-1206"))
    )
    (comp (ref "R61")
      (value "470")
      (footprint "eagle-import:1206")
      (libsource (lib "eagle-import") (part "PASSIF-RESISTOR-1206"))
    )
    (comp (ref "R62")
      (value "470")
      (footprint "eagle-import:1206")
      (libsource (lib "eagle-import") (part "PASSIF-RESISTOR-1206"))
    )
    (comp (ref "R63")
      (value "470")
      (footprint "eagle-import:1206")
      (libsource (lib "eagle-import") (part "PASSIF-RESISTOR-1206"))
    )
    (comp (ref "R64")
      (value "470")
      (footprint "eagle-import:1206")
      (libsource (lib "eagle-import") (part "PASSIF-RESISTOR-1206"))
    )
    (comp (ref "R65")
      (value "470")
      (footprint "eagle-import:1206")
      (libsource (lib "eagle-import") (part "PASSIF-RESISTOR-1206"))
    )
    (comp (ref "R66")
      (value "470")
      (footprint "eagle-import:1206")
      (libsource (lib "eagle-import") (part "PASSIF-RESISTOR-1206"))
    )
    (comp (ref "R67")
      (value "470")
      (footprint "eagle-import:1206")
      (libsource (lib "eagle-import") (part "PASSIF-RESISTOR-1206"))
    )
    (comp (ref "R68")
      (value "470")
      (footprint "eagle-import:1206")
      (libsource (lib "eagle-import") (part "PASSIF-RESISTOR-1206"))
    )
    (comp (ref "R69")
      (value "470")
      (footprint "eagle-import:1206")
      (libsource (lib "eagle-import") (part "PASSIF-RESISTOR-1206"))
    )
    (comp (ref "R70")
      (value "470")
      (footprint "eagle-import:1206")
      (libsource (lib "eagle-import") (part "PASSIF-RESISTOR-1206"))
    )
    (comp (ref "R71")
      (value "470")
      (footprint "eagle-import:1206")
      (libsource (lib "eagle-import") (part "PASSIF-RESISTOR-1206"))
    )
    (comp (ref "R72")
      (value "100")
      (footprint "eagle-import:1206")
      (libsource (lib "eagle-import") (part "PASSIF-RESISTOR-1206"))
    )
    (comp (ref "R73")
      (value "100")
      (footprint "eagle-import:1206")
      (libsource (lib "eagle-import") (part "PASSIF-RESISTOR-1206"))
    )
    (comp (ref "R74")
      (value "100")
      (footprint "eagle-import:1206")
      (libsource (lib "eagle-import") (part "PASSIF-RESISTOR-1206"))
    )
    (comp (ref "R75")
      (value "10k")
      (footprint "eagle-import:1206")
      (libsource (lib "eagle-import") (part "PASSIF-RESISTOR-1206"))
    )
    (comp (ref "R76")
      (value "100")
      (footprint "eagle-import:1206")
      (libsource (lib "eagle-import") (part "PASSIF-RESISTOR-1206"))
    )
    (comp (ref "R77")
      (value "100")
      (footprint "eagle-import:1206")
      (libsource (lib "eagle-import") (part "PASSIF-RESISTOR-1206"))
    )
    (comp (ref "R78")
      (value "100")
      (footprint "eagle-import:1206")
      (libsource (lib "eagle-import") (part "PASSIF-RESISTOR-1206"))
    )
    (comp (ref "R79")
      (value "10k")
      (footprint "eagle-import:1206")
      (libsource (lib "eagle-import") (part "PASSIF-RESISTOR-1206"))
    )
    (comp (ref "R80")
      (value "100")
      (footprint "eagle-import:1206")
      (libsource (lib "eagle-import") (part "PASSIF-RESISTOR-1206"))
    )
    (comp (ref "R81")
      (value "100")
      (footprint "eagle-import:1206")
      (libsource (lib "eagle-import") (part "PASSIF-RESISTOR-1206"))
    )
    (comp (ref "R82")
      (value "100")
      (footprint "eagle-import:1206")
      (libsource (lib "eagle-import") (part "PASSIF-RESISTOR-1206"))
    )
    (comp (ref "R83")
      (value "10k")
      (footprint "eagle-import:1206")
      (libsource (lib "eagle-import") (part "PASSIF-RESISTOR-1206"))
    )
    (comp (ref "R84")
      (value "100")
      (footprint "eagle-import:1206")
      (libsource (lib "eagle-import") (part "PASSIF-RESISTOR-1206"))
    )
    (comp (ref "R85")
      (value "100")
      (footprint "eagle-import:1206")
      (libsource (lib "eagle-import") (part "PASSIF-RESISTOR-1206"))
    )
    (comp (ref "R86")
      (value "100")
      (footprint "eagle-import:1206")
      (libsource (lib "eagle-import") (part "PASSIF-RESISTOR-1206"))
    )
    (comp (ref "R87")
      (value "10k")
      (footprint "eagle-import:1206")
      (libsource (lib "eagle-import") (part "PASSIF-RESISTOR-1206"))
    )
    (comp (ref "R88")
      (value "100")
      (footprint "eagle-import:1206")
      (libsource (lib "eagle-import") (part "PASSIF-RESISTOR-1206"))
    )
    (comp (ref "R89")
      (value "100")
      (footprint "eagle-import:1206")
      (libsource (lib "eagle-import") (part "PASSIF-RESISTOR-1206"))
    )
    (comp (ref "R90")
      (value "100")
      (footprint "eagle-import:1206")
      (libsource (lib "eagle-import") (part "PASSIF-RESISTOR-1206"))
    )
    (comp (ref "R91")
      (value "10k")
      (footprint "eagle-import:1206")
      (libsource (lib "eagle-import") (part "PASSIF-RESISTOR-1206"))
    )
    (comp (ref "R92")
      (value "100")
      (footprint "eagle-import:1206")
      (libsource (lib "eagle-import") (part "PASSIF-RESISTOR-1206"))
    )
    (comp (ref "R93")
      (value "100")
      (footprint "eagle-import:1206")
      (libsource (lib "eagle-import") (part "PASSIF-RESISTOR-1206"))
    )
    (comp (ref "R94")
      (value "100")
      (footprint "eagle-import:1206")
      (libsource (lib "eagle-import") (part "PASSIF-RESISTOR-1206"))
    )
    (comp (ref "R95")
      (value "10k")
      (footprint "eagle-import:1206")
      (libsource (lib "eagle-import") (part "PASSIF-RESISTOR-1206"))
    )
    (comp (ref "R96")
      (value "100")
      (footprint "eagle-import:1206")
      (libsource (lib "eagle-import") (part "PASSIF-RESISTOR-1206"))
    )
    (comp (ref "R97")
      (value "100")
      (footprint "eagle-import:1206")
      (libsource (lib "eagle-import") (part "PASSIF-RESISTOR-1206"))
    )
    (comp (ref "R98")
      (value "100")
      (footprint "eagle-import:1206")
      (libsource (lib "eagle-import") (part "PASSIF-RESISTOR-1206"))
    )
    (comp (ref "R99")
      (value "10k")
      (footprint "eagle-import:1206")
      (libsource (lib "eagle-import") (part "PASSIF-RESISTOR-1206"))
    )
    (comp (ref "R100")
      (value "100")
      (footprint "eagle-import:1206")
      (libsource (lib "eagle-import") (part "PASSIF-RESISTOR-1206"))
    )
    (comp (ref "R101")
      (value "100")
      (footprint "eagle-import:1206")
      (libsource (lib "eagle-import") (part "PASSIF-RESISTOR-1206"))
    )
    (comp (ref "R102")
      (value "100")
      (footprint "eagle-import:1206")
      (libsource (lib "eagle-import") (part "PASSIF-RESISTOR-1206"))
    )
    (comp (ref "R103")
      (value "10k")
      (footprint "eagle-import:1206")
      (libsource (lib "eagle-import") (part "PASSIF-RESISTOR-1206"))
    )
    (comp (ref "S7")
      (value "ENCODER-RGB-SWITCH-NO_NUT")
      (footprint "eagle-import:ENCODER_LED_3")
      (libsource (lib "eagle-import") (part "ENCODER-RGB-SWITCH-NO_NUT"))
    )
    (comp (ref "S8")
      (value "ENCODER-RGB-SWITCH-NO_NUT")
      (footprint "eagle-import:ENCODER_LED_3")
      (libsource (lib "eagle-import") (part "ENCODER-RGB-SWITCH-NO_NUT"))
    )
    (comp (ref "S9")
      (value "ENCODER-RGB-SWITCH-NO_NUT")
      (footprint "eagle-import:ENCODER_LED_3")
      (libsource (lib "eagle-import") (part "ENCODER-RGB-SWITCH-NO_NUT"))
    )
    (comp (ref "S10")
      (value "ENCODER-RGB-SWITCH-NO_NUT")
      (footprint "eagle-import:ENCODER_LED_3")
      (libsource (lib "eagle-import") (part "ENCODER-RGB-SWITCH-NO_NUT"))
    )
    (comp (ref "S11")
      (value "ENCODER-RGB-SWITCH-NO_NUT")
      (footprint "eagle-import:ENCODER_LED_3")
      (libsource (lib "eagle-import") (part "ENCODER-RGB-SWITCH-NO_NUT"))
    )
    (comp (ref "S12")
      (value "ENCODER-RGB-SWITCH-NO_NUT")
      (footprint "eagle-import:ENCODER_LED_3")
      (libsource (lib "eagle-import") (part "ENCODER-RGB-SWITCH-NO_NUT"))
    )
    (comp (ref "S13")
      (value "ENCODER-RGB-SWITCH-NO_NUT")
      (footprint "eagle-import:ENCODER_LED_3")
      (libsource (lib "eagle-import") (part "ENCODER-RGB-SWITCH-NO_NUT"))
    )
    (comp (ref "S14")
      (value "ENCODER-RGB-SWITCH-NO_NUT")
      (footprint "eagle-import:ENCODER_LED_3")
      (libsource (lib "eagle-import") (part "ENCODER-RGB-SWITCH-NO_NUT"))
    )
  )
  (nets
    (net (code "1") (name "3V3") (class "Default")
      (node (ref "C10") (pin "2") (pinfunction "2_2") (pintype "passive"))
      (node (ref "C11") (pin "2") (pinfunction "2_2") (pintype "passive"))
      (node (ref "C12") (pin "1") (pinfunction "1_1") (pintype "passive"))
      (node (ref "C13") (pin "+") (pinfunction "+_+") (pintype "passive"))
      (node (ref "C14") (pin "+") (pinfunction "+_+") (pintype "passive"))
      (node (ref "C15") (pin "+") (pinfunction "+_+") (pintype "passive"))
      (node (ref "C16") (pin "+") (pinfunction "+_+") (pintype "passive"))
      (node (ref "C17") (pin "+") (pinfunction "+_+") (pintype "passive"))
      (node (ref "C18") (pin "+") (pinfunction "+_+") (pintype "passive"))
      (node (ref "C29") (pin "1") (pinfunction "1_1") (pintype "passive"))
      (node (ref "C30") (pin "1") (pinfunction "1_1") (pintype "passive"))
      (node (ref "C31") (pin "1") (pinfunction "1_1") (pintype "passive"))
      (node (ref "C32") (pin "1") (pinfunction "1_1") (pintype "passive"))
      (node (ref "C33") (pin "1") (pinfunction "1_1") (pintype "passive"))
      (node (ref "C39") (pin "1") (pinfunction "1_1") (pintype "passive"))
      (node (ref "C4") (pin "+") (pinfunction "+_+") (pintype "passive"))
      (node (ref "C40") (pin "+") (pinfunction "+_+") (pintype "passive"))
      (node (ref "C41") (pin "+") (pinfunction "+_+") (pintype "passive"))
      (node (ref "C42") (pin "1") (pinfunction "1_1") (pintype "passive"))
      (node (ref "C43") (pin "+") (pinfunction "+_+") (pintype "passive"))
      (node (ref "C44") (pin "+") (pinfunction "+_+") (pintype "passive"))
      (node (ref "C45") (pin "+") (pinfunction "+_+") (pintype "passive"))
      (node (ref "C46") (pin "+") (pinfunction "+_+") (pintype "passive"))
      (node (ref "C47") (pin "+") (pinfunction "+_+") (pintype "passive"))
      (node (ref "C48") (pin "+") (pinfunction "+_+") (pintype "passive"))
      (node (ref "C49") (pin "+") (pinfunction "+_+") (pintype "passive"))
      (node (ref "C50") (pin "+") (pinfunction "+_+") (pintype "passive"))
      (node (ref "C6") (pin "2") (pinfunction "2_2") (pintype "passive"))
      (node (ref "C67") (pin "1") (pinfunction "1_1") (pintype "passive"))
      (node (ref "C68") (pin "1") (pinfunction "1_1") (pintype "passive"))
      (node (ref "C69") (pin "1") (pinfunction "1_1") (pintype "passive"))
      (node (ref "C7") (pin "2") (pinfunction "2_2") (pintype "passive"))
      (node (ref "C70") (pin "1") (pinfunction "1_1") (pintype "passive"))
      (node (ref "C71") (pin "1") (pinfunction "1_1") (pintype "passive"))
      (node (ref "C72") (pin "1") (pinfunction "1_1") (pintype "passive"))
      (node (ref "C73") (pin "1") (pinfunction "1_1") (pintype "passive"))
      (node (ref "C74") (pin "1") (pinfunction "1_1") (pintype "passive"))
      (node (ref "C8") (pin "2") (pinfunction "2_2") (pintype "passive"))
      (node (ref "C9") (pin "2") (pinfunction "2_2") (pintype "passive"))
      (node (ref "CON_STH_BRD") (pin "2") (pinfunction "2_2") (pintype "passive"))
      (node (ref "CON_STH_BRD") (pin "4") (pinfunction "4_4") (pintype "passive"))
      (node (ref "CON_TFT_EXT") (pin "1") (pinfunction "1_1") (pintype "passive"))
      (node (ref "F446") (pin "1") (pinfunction "VBAT_1") (pintype "power_in"))
      (node (ref "F446") (pin "13") (pinfunction "VDDA/VREF+_13") (pintype "power_in"))
      (node (ref "F446") (pin "19") (pinfunction "VDD_4_19") (pintype "power_in"))
      (node (ref "F446") (pin "32") (pinfunction "VDD_1_32") (pintype "power_in"))
      (node (ref "F446") (pin "48") (pinfunction "VDD_2_48") (pintype "power_in"))
      (node (ref "F446") (pin "64") (pinfunction "VDD_3_64") (pintype "power_in"))
      (node (ref "L1") (pin "2") (pinfunction "2_2") (pintype "passive"))
      (node (ref "MCP_101") (pin "15") (pinfunction "A0_15") (pintype "bidirectional"))
      (node (ref "MCP_101") (pin "17") (pinfunction "A2_17") (pintype "bidirectional"))
      (node (ref "MCP_101") (pin "9") (pinfunction "VDD_9") (pintype "bidirectional"))
      (node (ref "MCP_110") (pin "16") (pinfunction "A1_16") (pintype "bidirectional"))
      (node (ref "MCP_110") (pin "17") (pinfunction "A2_17") (pintype "bidirectional"))
      (node (ref "MCP_110") (pin "9") (pinfunction "VDD_9") (pintype "bidirectional"))
      (node (ref "MCP_111") (pin "15") (pinfunction "A0_15") (pintype "bidirectional"))
      (node (ref "MCP_111") (pin "16") (pinfunction "A1_16") (pintype "bidirectional"))
      (node (ref "MCP_111") (pin "17") (pinfunction "A2_17") (pintype "bidirectional"))
      (node (ref "MCP_111") (pin "9") (pinfunction "VDD_9") (pintype "bidirectional"))
      (node (ref "PX_BF") (pin "8") (pinfunction "VCC_8") (pintype "bidirectional"))
      (node (ref "PX_CHORUS") (pin "8") (pinfunction "VCC_8") (pintype "bidirectional"))
      (node (ref "PX_DELAY") (pin "8") (pinfunction "VCC_8") (pintype "bidirectional"))
      (node (ref "PX_DRIVE") (pin "8") (pinfunction "VCC_8") (pintype "bidirectional"))
      (node (ref "PX_HUMAN") (pin "8") (pinfunction "VCC_8") (pintype "bidirectional"))
      (node (ref "PX_LATCH") (pin "8") (pinfunction "VCC_8") (pintype "bidirectional"))
      (node (ref "PX_ONOFF") (pin "8") (pinfunction "VCC_8") (pintype "bidirectional"))
      (node (ref "PX_PATTERN") (pin "8") (pinfunction "VCC_8") (pintype "bidirectional"))
      (node (ref "PX_PORTA") (pin "8") (pinfunction "VCC_8") (pintype "bidirectional"))
      (node (ref "PX_RANGE") (pin "8") (pinfunction "VCC_8") (pintype "bidirectional"))
      (node (ref "PX_RATE") (pin "8") (pinfunction "VCC_8") (pintype "bidirectional"))
      (node (ref "PX_REVERB") (pin "8") (pinfunction "VCC_8") (pintype "bidirectional"))
      (node (ref "PX_SYNC") (pin "8") (pinfunction "VCC_8") (pintype "bidirectional"))
      (node (ref "R2") (pin "1") (pinfunction "1_1") (pintype "passive"))
      (node (ref "R44") (pin "2") (pinfunction "2_2") (pintype "passive"))
      (node (ref "R45") (pin "2") (pinfunction "2_2") (pintype "passive"))
      (node (ref "R46") (pin "2") (pinfunction "2_2") (pintype "passive"))
      (node (ref "R47") (pin "2") (pinfunction "2_2") (pintype "passive"))
      (node (ref "R5") (pin "1") (pinfunction "1_1") (pintype "passive"))
      (node (ref "R7") (pin "2") (pinfunction "2_2") (pintype "passive"))
      (node (ref "R8") (pin "2") (pinfunction "2_2") (pintype "passive"))
      (node (ref "S10") (pin "5") (pinfunction "+_5") (pintype "passive"))
      (node (ref "S11") (pin "5") (pinfunction "+_5") (pintype "passive"))
      (node (ref "S12") (pin "5") (pinfunction "+_5") (pintype "passive"))
      (node (ref "S13") (pin "5") (pinfunction "+_5") (pintype "passive"))
      (node (ref "S14") (pin "5") (pinfunction "+_5") (pintype "passive"))
      (node (ref "S2") (pin "5") (pinfunction "+_5") (pintype "passive"))
      (node (ref "S3") (pin "5") (pinfunction "+_5") (pintype "passive"))
      (node (ref "S4") (pin "5") (pinfunction "+_5") (pintype "passive"))
      (node (ref "S5") (pin "5") (pinfunction "+_5") (pintype "passive"))
      (node (ref "S6") (pin "5") (pinfunction "+_5") (pintype "passive"))
      (node (ref "S7") (pin "5") (pinfunction "+_5") (pintype "passive"))
      (node (ref "S8") (pin "5") (pinfunction "+_5") (pintype "passive"))
      (node (ref "S9") (pin "5") (pinfunction "+_5") (pintype "passive"))
      (node (ref "STLINK") (pin "1") (pinfunction "1_1") (pintype "passive"))
    )
    (net (code "2") (name "5V") (class "Default")
      (node (ref "0V/5V") (pin "3") (pinfunction "3_3") (pintype "passive"))
      (node (ref "0V/5V") (pin "4") (pinfunction "4_4") (pintype "passive"))
      (node (ref "C3") (pin "+") (pinfunction "+_+") (pintype "passive"))
      (node (ref "C5") (pin "2") (pinfunction "2_2") (pintype "passive"))
      (node (ref "R6") (pin "1") (pinfunction "1_1") (pintype "passive"))
      (node (ref "REG") (pin "1") (pinfunction "IN_1") (pintype "input"))
      (node (ref "REG") (pin "3") (pinfunction "EN_3") (pintype "input"))
    )
    (net (code "3") (name "ADC1_IN1") (class "Default")
      (node (ref "AIN") (pin "4") (pinfunction "4_4") (pintype "passive"))
      (node (ref "F446") (pin "15") (pinfunction "PA1_15") (pintype "bidirectional"))
    )
    (net (code "4") (name "ADC1_IN4") (class "Default")
      (node (ref "AIN") (pin "3") (pinfunction "3_3") (pintype "passive"))
      (node (ref "F446") (pin "20") (pinfunction "PA4_20") (pintype "bidirectional"))
    )
    (net (code "5") (name "ADC1_IN10") (class "Default")
      (node (ref "AIN") (pin "2") (pinfunction "2_2") (pintype "passive"))
      (node (ref "F446") (pin "8") (pinfunction "PC0_8") (pintype "bidirectional"))
    )
    (net (code "6") (name "GND") (class "Default")
      (node (ref "0V/5V") (pin "1") (pinfunction "1_1") (pintype "passive"))
      (node (ref "0V/5V") (pin "2") (pinfunction "2_2") (pintype "passive"))
      (node (ref "AIN") (pin "1") (pinfunction "1_1") (pintype "passive"))
      (node (ref "ANALOG") (pin "1") (pinfunction "1_1") (pintype "passive"))
      (node (ref "C1") (pin "1") (pinfunction "1_1") (pintype "passive"))
      (node (ref "C10") (pin "1") (pinfunction "1_1") (pintype "passive"))
      (node (ref "C11") (pin "1") (pinfunction "1_1") (pintype "passive"))
      (node (ref "C12") (pin "2") (pinfunction "2_2") (pintype "passive"))
      (node (ref "C13") (pin "-") (pinfunction "-_-") (pintype "passive"))
      (node (ref "C14") (pin "-") (pinfunction "-_-") (pintype "passive"))
      (node (ref "C15") (pin "-") (pinfunction "-_-") (pintype "passive"))
      (node (ref "C16") (pin "-") (pinfunction "-_-") (pintype "passive"))
      (node (ref "C17") (pin "-") (pinfunction "-_-") (pintype "passive"))
      (node (ref "C18") (pin "-") (pinfunction "-_-") (pintype "passive"))
      (node (ref "C19") (pin "1") (pinfunction "1_1") (pintype "passive"))
      (node (ref "C2") (pin "1") (pinfunction "1_1") (pintype "passive"))
      (node (ref "C20") (pin "1") (pinfunction "1_1") (pintype "passive"))
      (node (ref "C21") (pin "1") (pinfunction "1_1") (pintype "passive"))
      (node (ref "C22") (pin "1") (pinfunction "1_1") (pintype "passive"))
      (node (ref "C23") (pin "1") (pinfunction "1_1") (pintype "passive"))
      (node (ref "C24") (pin "1") (pinfunction "1_1") (pintype "passive"))
      (node (ref "C25") (pin "1") (pinfunction "1_1") (pintype "passive"))
      (node (ref "C26") (pin "1") (pinfunction "1_1") (pintype "passive"))
      (node (ref "C27") (pin "1") (pinfunction "1_1") (pintype "passive"))
      (node (ref "C28") (pin "1") (pinfunction "1_1") (pintype "passive"))
      (node (ref "C29") (pin "2") (pinfunction "2_2") (pintype "passive"))
      (node (ref "C3") (pin "-") (pinfunction "-_-") (pintype "passive"))
      (node (ref "C30") (pin "2") (pinfunction "2_2") (pintype "passive"))
      (node (ref "C31") (pin "2") (pinfunction "2_2") (pintype "passive"))
      (node (ref "C32") (pin "2") (pinfunction "2_2") (pintype "passive"))
      (node (ref "C33") (pin "2") (pinfunction "2_2") (pintype "passive"))
      (node (ref "C34") (pin "2") (pinfunction "2_2") (pintype "passive"))
      (node (ref "C35") (pin "2") (pinfunction "2_2") (pintype "passive"))
      (node (ref "C36") (pin "2") (pinfunction "2_2") (pintype "passive"))
      (node (ref "C37") (pin "2") (pinfunction "2_2") (pintype "passive"))
      (node (ref "C38") (pin "2") (pinfunction "2_2") (pintype "passive"))
      (node (ref "C39") (pin "2") (pinfunction "2_2") (pintype "passive"))
      (node (ref "C4") (pin "-") (pinfunction "-_-") (pintype "passive"))
      (node (ref "C40") (pin "-") (pinfunction "-_-") (pintype "passive"))
      (node (ref "C41") (pin "-") (pinfunction "-_-") (pintype "passive"))
      (node (ref "C42") (pin "2") (pinfunction "2_2") (pintype "passive"))
      (node (ref "C43") (pin "-") (pinfunction "-_-") (pintype "passive"))
      (node (ref "C44") (pin "-") (pinfunction "-_-") (pintype "passive"))
      (node (ref "C45") (pin "-") (pinfunction "-_-") (pintype "passive"))
      (node (ref "C46") (pin "-") (pinfunction "-_-") (pintype "passive"))
      (node (ref "C47") (pin "-") (pinfunction "-_-") (pintype "passive"))
      (node (ref "C48") (pin "-") (pinfunction "-_-") (pintype "passive"))
      (node (ref "C49") (pin "-") (pinfunction "-_-") (pintype "passive"))
      (node (ref "C5") (pin "1") (pinfunction "1_1") (pintype "passive"))
      (node (ref "C50") (pin "-") (pinfunction "-_-") (pintype "passive"))
      (node (ref "C51") (pin "1") (pinfunction "1_1") (pintype "passive"))
      (node (ref "C52") (pin "1") (pinfunction "1_1") (pintype "passive"))
      (node (ref "C53") (pin "1") (pinfunction "1_1") (pintype "passive"))
      (node (ref "C54") (pin "1") (pinfunction "1_1") (pintype "passive"))
      (node (ref "C55") (pin "1") (pinfunction "1_1") (pintype "passive"))
      (node (ref "C56") (pin "1") (pinfunction "1_1") (pintype "passive"))
      (node (ref "C57") (pin "1") (pinfunction "1_1") (pintype "passive"))
      (node (ref "C58") (pin "1") (pinfunction "1_1") (pintype "passive"))
      (node (ref "C59") (pin "1") (pinfunction "1_1") (pintype "passive"))
      (node (ref "C6") (pin "1") (pinfunction "1_1") (pintype "passive"))
      (node (ref "C60") (pin "1") (pinfunction "1_1") (pintype "passive"))
      (node (ref "C61") (pin "1") (pinfunction "1_1") (pintype "passive"))
      (node (ref "C62") (pin "1") (pinfunction "1_1") (pintype "passive"))
      (node (ref "C63") (pin "1") (pinfunction "1_1") (pintype "passive"))
      (node (ref "C64") (pin "1") (pinfunction "1_1") (pintype "passive"))
      (node (ref "C65") (pin "1") (pinfunction "1_1") (pintype "passive"))
      (node (ref "C66") (pin "1") (pinfunction "1_1") (pintype "passive"))
      (node (ref "C67") (pin "2") (pinfunction "2_2") (pintype "passive"))
      (node (ref "C68") (pin "2") (pinfunction "2_2") (pintype "passive"))
      (node (ref "C69") (pin "2") (pinfunction "2_2") (pintype "passive"))
      (node (ref "C7") (pin "1") (pinfunction "1_1") (pintype "passive"))
      (node (ref "C70") (pin "2") (pinfunction "2_2") (pintype "passive"))
      (node (ref "C71") (pin "2") (pinfunction "2_2") (pintype "passive"))
      (node (ref "C72") (pin "2") (pinfunction "2_2") (pintype "passive"))
      (node (ref "C73") (pin "2") (pinfunction "2_2") (pintype "passive"))
      (node (ref "C74") (pin "2") (pinfunction "2_2") (pintype "passive"))
      (node (ref "C75") (pin "2") (pinfunction "2_2") (pintype "passive"))
      (node (ref "C76") (pin "2") (pinfunction "2_2") (pintype "passive"))
      (node (ref "C77") (pin "2") (pinfunction "2_2") (pintype "passive"))
      (node (ref "C78") (pin "2") (pinfunction "2_2") (pintype "passive"))
      (node (ref "C79") (pin "2") (pinfunction "2_2") (pintype "passive"))
      (node (ref "C8") (pin "1") (pinfunction "1_1") (pintype "passive"))
      (node (ref "C80") (pin "2") (pinfunction "2_2") (pintype "passive"))
      (node (ref "C81") (pin "2") (pinfunction "2_2") (pintype "passive"))
      (node (ref "C82") (pin "2") (pinfunction "2_2") (pintype "passive"))
      (node (ref "C9") (pin "1") (pinfunction "1_1") (pintype "passive"))
      (node (ref "CON_STH_BRD") (pin "1") (pinfunction "1_1") (pintype "passive"))
      (node (ref "CON_TFT_EXT") (pin "7") (pinfunction "7_7") (pintype "passive"))
      (node (ref "DISCO") (pin "1") (pinfunction "1_1") (pintype "passive"))
      (node (ref "F446") (pin "12") (pinfunction "VSSA/VREF-_12") (pintype "power_in"))
      (node (ref "F446") (pin "18") (pinfunction "VSS_4_18") (pintype "power_in"))
      (node (ref "F446") (pin "31") (pinfunction "VSS_1_31") (pintype "power_in"))
      (node (ref "F446") (pin "47") (pinfunction "VSS_2_47") (pintype "power_in"))
      (node (ref "F446") (pin "63") (pinfunction "VSS_3_63") (pintype "power_in"))
      (node (ref "LD_3V") (pin "C") (pinfunction "C_C") (pintype "passive"))
      (node (ref "LD_5V") (pin "C") (pinfunction "C_C") (pintype "passive"))
      (node (ref "LD_GR") (pin "C") (pinfunction "C_C") (pintype "passive"))
      (node (ref "MCP_101") (pin "10") (pinfunction "VSS_10") (pintype "bidirectional"))
      (node (ref "MCP_101") (pin "16") (pinfunction "A1_16") (pintype "bidirectional"))
      (node (ref "MCP_110") (pin "10") (pinfunction "VSS_10") (pintype "bidirectional"))
      (node (ref "MCP_110") (pin "15") (pinfunction "A0_15") (pintype "bidirectional"))
      (node (ref "MCP_111") (pin "10") (pinfunction "VSS_10") (pintype "bidirectional"))
      (node (ref "MIDI") (pin "1") (pinfunction "1_1") (pintype "passive"))
      (node (ref "NRST") (pin "1") (pinfunction "1_1") (pintype "bidirectional"))
      (node (ref "PX_BF") (pin "4") (pinfunction "GND_4") (pintype "bidirectional"))
      (node (ref "PX_CHORUS") (pin "4") (pinfunction "GND_4") (pintype "bidirectional"))
      (node (ref "PX_DELAY") (pin "4") (pinfunction "GND_4") (pintype "bidirectional"))
      (node (ref "PX_DRIVE") (pin "4") (pinfunction "GND_4") (pintype "bidirectional"))
      (node (ref "PX_HUMAN") (pin "4") (pinfunction "GND_4") (pintype "bidirectional"))
      (node (ref "PX_LATCH") (pin "4") (pinfunction "GND_4") (pintype "bidirectional"))
      (node (ref "PX_ONOFF") (pin "4") (pinfunction "GND_4") (pintype "bidirectional"))
      (node (ref "PX_PATTERN") (pin "4") (pinfunction "GND_4") (pintype "bidirectional"))
      (node (ref "PX_PORTA") (pin "4") (pinfunction "GND_4") (pintype "bidirectional"))
      (node (ref "PX_RANGE") (pin "4") (pinfunction "GND_4") (pintype "bidirectional"))
      (node (ref "PX_RATE") (pin "4") (pinfunction "GND_4") (pintype "bidirectional"))
      (node (ref "PX_REVERB") (pin "4") (pinfunction "GND_4") (pintype "bidirectional"))
      (node (ref "PX_SYNC") (pin "4") (pinfunction "GND_4") (pintype "bidirectional"))
      (node (ref "R103") (pin "2") (pinfunction "2_2") (pintype "passive"))
      (node (ref "R27") (pin "2") (pinfunction "2_2") (pintype "passive"))
      (node (ref "R3") (pin "2") (pinfunction "2_2") (pintype "passive"))
      (node (ref "R31") (pin "2") (pinfunction "2_2") (pintype "passive"))
      (node (ref "R35") (pin "2") (pinfunction "2_2") (pintype "passive"))
      (node (ref "R39") (pin "2") (pinfunction "2_2") (pintype "passive"))
      (node (ref "R43") (pin "2") (pinfunction "2_2") (pintype "passive"))
      (node (ref "R75") (pin "2") (pinfunction "2_2") (pintype "passive"))
      (node (ref "R79") (pin "2") (pinfunction "2_2") (pintype "passive"))
      (node (ref "R83") (pin "2") (pinfunction "2_2") (pintype "passive"))
      (node (ref "R87") (pin "2") (pinfunction "2_2") (pintype "passive"))
      (node (ref "R91") (pin "2") (pinfunction "2_2") (pintype "passive"))
      (node (ref "R95") (pin "2") (pinfunction "2_2") (pintype "passive"))
      (node (ref "R99") (pin "2") (pinfunction "2_2") (pintype "passive"))
      (node (ref "REG") (pin "2") (pinfunction "GND_2") (pintype "power_in"))
      (node (ref "S10") (pin "C") (pinfunction "C_C") (pintype "bidirectional"))
      (node (ref "S11") (pin "C") (pinfunction "C_C") (pintype "bidirectional"))
      (node (ref "S12") (pin "C") (pinfunction "C_C") (pintype "bidirectional"))
      (node (ref "S13") (pin "C") (pinfunction "C_C") (pintype "bidirectional"))
      (node (ref "S14") (pin "C") (pinfunction "C_C") (pintype "bidirectional"))
      (node (ref "S2") (pin "C") (pinfunction "C_C") (pintype "bidirectional"))
      (node (ref "S3") (pin "C") (pinfunction "C_C") (pintype "bidirectional"))
      (node (ref "S4") (pin "C") (pinfunction "C_C") (pintype "bidirectional"))
      (node (ref "S5") (pin "C") (pinfunction "C_C") (pintype "bidirectional"))
      (node (ref "S6") (pin "C") (pinfunction "C_C") (pintype "bidirectional"))
      (node (ref "S7") (pin "C") (pinfunction "C_C") (pintype "bidirectional"))
      (node (ref "S8") (pin "C") (pinfunction "C_C") (pintype "bidirectional"))
      (node (ref "S9") (pin "C") (pinfunction "C_C") (pintype "bidirectional"))
      (node (ref "STLINK") (pin "5") (pinfunction "5_5") (pintype "passive"))
    )
    (net (code "7") (name "GPA0_5") (class "Default")
      (node (ref "MCP_111") (pin "21") (pinfunction "GPA0_21") (pintype "bidirectional"))
      (node (ref "R20") (pin "1") (pinfunction "1_1") (pintype "passive"))
      (node (ref "R31") (pin "1") (pinfunction "1_1") (pintype "passive"))
      (node (ref "S3") (pin "3") (pinfunction "SW_3") (pintype "passive"))
    )
    (net (code "8") (name "GPA0_41") (class "Default")
      (node (ref "MCP_101") (pin "21") (pinfunction "GPA0_21") (pintype "bidirectional"))
      (node (ref "R103") (pin "1") (pinfunction "1_1") (pintype "passive"))
      (node (ref "R71") (pin "1") (pinfunction "1_1") (pintype "passive"))
      (node (ref "S14") (pin "3") (pinfunction "SW_3") (pintype "passive"))
    )
    (net (code "9") (name "GPA0_42") (class "Default")
      (node (ref "MCP_110") (pin "21") (pinfunction "GPA0_21") (pintype "bidirectional"))
      (node (ref "R58") (pin "1") (pinfunction "1_1") (pintype "passive"))
      (node (ref "S12") (pin "A") (pinfunction "A_A") (pintype "bidirectional"))
    )
    (net (code "10") (name "GPA1_5") (class "Default")
      (node (ref "MCP_111") (pin "22") (pinfunction "GPA1_22") (pintype "bidirectional"))
      (node (ref "R12") (pin "1") (pinfunction "1_1") (pintype "passive"))
      (node (ref "S3") (pin "B") (pinfunction "B_B") (pintype "bidirectional"))
    )
    (net (code "11") (name "GPA1_41") (class "Default")
      (node (ref "MCP_101") (pin "22") (pinfunction "GPA1_22") (pintype "bidirectional"))
      (node (ref "R70") (pin "1") (pinfunction "1_1") (pintype "passive"))
      (node (ref "R99") (pin "1") (pinfunction "1_1") (pintype "passive"))
      (node (ref "S13") (pin "3") (pinfunction "SW_3") (pintype "passive"))
    )
    (net (code "12") (name "GPA1_42") (class "Default")
      (node (ref "MCP_110") (pin "22") (pinfunction "GPA1_22") (pintype "bidirectional"))
      (node (ref "R59") (pin "1") (pinfunction "1_1") (pintype "passive"))
      (node (ref "S12") (pin "B") (pinfunction "B_B") (pintype "bidirectional"))
    )
    (net (code "13") (name "GPA2_5") (class "Default")
      (node (ref "MCP_111") (pin "23") (pinfunction "GPA2_23") (pintype "bidirectional"))
      (node (ref "R11") (pin "1") (pinfunction "1_1") (pintype "passive"))
      (node (ref "S3") (pin "A") (pinfunction "A_A") (pintype "bidirectional"))
    )
    (net (code "14") (name "GPA2_41") (class "Default")
      (node (ref "MCP_101") (pin "23") (pinfunction "GPA2_23") (pintype "bidirectional"))
      (node (ref "R60") (pin "1") (pinfunction "1_1") (pintype "passive"))
      (node (ref "S13") (pin "A") (pinfunction "A_A") (pintype "bidirectional"))
    )
    (net (code "15") (name "GPA2_42") (class "Default")
      (node (ref "MCP_110") (pin "23") (pinfunction "GPA2_23") (pintype "bidirectional"))
      (node (ref "R56") (pin "1") (pinfunction "1_1") (pintype "passive"))
      (node (ref "S11") (pin "A") (pinfunction "A_A") (pintype "bidirectional"))
    )
    (net (code "16") (name "GPA3_5") (class "Default")
      (node (ref "MCP_111") (pin "24") (pinfunction "GPA3_24") (pintype "bidirectional"))
      (node (ref "R21") (pin "1") (pinfunction "1_1") (pintype "passive"))
      (node (ref "R35") (pin "1") (pinfunction "1_1") (pintype "passive"))
      (node (ref "S4") (pin "3") (pinfunction "SW_3") (pintype "passive"))
    )
    (net (code "17") (name "GPA3_41") (class "Default")
      (node (ref "MCP_101") (pin "24") (pinfunction "GPA3_24") (pintype "bidirectional"))
      (node (ref "R61") (pin "1") (pinfunction "1_1") (pintype "passive"))
      (node (ref "S13") (pin "B") (pinfunction "B_B") (pintype "bidirectional"))
    )
    (net (code "18") (name "GPA3_42") (class "Default")
      (node (ref "MCP_110") (pin "24") (pinfunction "GPA3_24") (pintype "bidirectional"))
      (node (ref "R57") (pin "1") (pinfunction "1_1") (pintype "passive"))
      (node (ref "S11") (pin "B") (pinfunction "B_B") (pintype "bidirectional"))
    )
    (net (code "19") (name "GPA4_5") (class "Default")
      (node (ref "MCP_111") (pin "25") (pinfunction "GPA4_25") (pintype "bidirectional"))
      (node (ref "R52") (pin "1") (pinfunction "1_1") (pintype "passive"))
      (node (ref "S9") (pin "A") (pinfunction "A_A") (pintype "bidirectional"))
    )
    (net (code "20") (name "GPA4_41") (class "Default")
      (node (ref "MCP_101") (pin "25") (pinfunction "GPA4_25") (pintype "bidirectional"))
      (node (ref "R69") (pin "1") (pinfunction "1_1") (pintype "passive"))
      (node (ref "R95") (pin "1") (pinfunction "1_1") (pintype "passive"))
      (node (ref "S12") (pin "3") (pinfunction "SW_3") (pintype "passive"))
    )
    (net (code "21") (name "GPA4_42") (class "Default")
      (node (ref "MCP_110") (pin "25") (pinfunction "GPA4_25") (pintype "bidirectional"))
      (node (ref "R68") (pin "1") (pinfunction "1_1") (pintype "passive"))
      (node (ref "R91") (pin "1") (pinfunction "1_1") (pintype "passive"))
      (node (ref "S11") (pin "3") (pinfunction "SW_3") (pintype "passive"))
    )
    (net (code "22") (name "GPA5_5") (class "Default")
      (node (ref "MCP_111") (pin "26") (pinfunction "GPA5_26") (pintype "bidirectional"))
      (node (ref "R53") (pin "1") (pinfunction "1_1") (pintype "passive"))
      (node (ref "S9") (pin "B") (pinfunction "B_B") (pintype "bidirectional"))
    )
    (net (code "23") (name "GPA5_41") (class "Default")
      (node (ref "CON_TFT_EXT") (pin "5") (pinfunction "5_5") (pintype "passive"))
      (node (ref "MCP_101") (pin "26") (pinfunction "GPA5_26") (pintype "bidirectional"))
    )
    (net (code "24") (name "GPA5_42") (class "Default")
      (node (ref "MCP_110") (pin "26") (pinfunction "GPA5_26") (pintype "bidirectional"))
      (node (ref "R54") (pin "1") (pinfunction "1_1") (pintype "passive"))
      (node (ref "S10") (pin "A") (pinfunction "A_A") (pintype "bidirectional"))
    )
    (net (code "25") (name "GPA6_5") (class "Default")
      (node (ref "MCP_111") (pin "27") (pinfunction "GPA6_27") (pintype "bidirectional"))
      (node (ref "R66") (pin "1") (pinfunction "1_1") (pintype "passive"))
      (node (ref "R83") (pin "1") (pinfunction "1_1") (pintype "passive"))
      (node (ref "S9") (pin "3") (pinfunction "SW_3") (pintype "passive"))
    )
    (net (code "26") (name "GPA6_41") (class "Default")
      (node (ref "CON_TFT_EXT") (pin "3") (pinfunction "3_3") (pintype "passive"))
      (node (ref "MCP_101") (pin "27") (pinfunction "GPA6_27") (pintype "bidirectional"))
    )
    (net (code "27") (name "GPA6_42") (class "Default")
      (node (ref "MCP_110") (pin "27") (pinfunction "GPA6_27") (pintype "bidirectional"))
      (node (ref "R55") (pin "1") (pinfunction "1_1") (pintype "passive"))
      (node (ref "S10") (pin "B") (pinfunction "B_B") (pintype "bidirectional"))
    )
    (net (code "28") (name "GPA7_5") (class "Default")
      (node (ref "MCP_111") (pin "28") (pinfunction "GPA7_28") (pintype "bidirectional"))
      (node (ref "R65") (pin "1") (pinfunction "1_1") (pintype "passive"))
      (node (ref "R79") (pin "1") (pinfunction "1_1") (pintype "passive"))
      (node (ref "S8") (pin "3") (pinfunction "SW_3") (pintype "passive"))
    )
    (net (code "29") (name "GPA7_41") (class "Default")
      (node (ref "CON_TFT_EXT") (pin "2") (pinfunction "2_2") (pintype "passive"))
      (node (ref "MCP_101") (pin "28") (pinfunction "GPA7_28") (pintype "bidirectional"))
    )
    (net (code "30") (name "GPA7_42") (class "Default")
      (node (ref "MCP_110") (pin "28") (pinfunction "GPA7_28") (pintype "bidirectional"))
      (node (ref "R67") (pin "1") (pinfunction "1_1") (pintype "passive"))
      (node (ref "R87") (pin "1") (pinfunction "1_1") (pintype "passive"))
      (node (ref "S10") (pin "3") (pinfunction "SW_3") (pintype "passive"))
    )
    (net (code "31") (name "GPB0_5") (class "Default")
      (node (ref "MCP_111") (pin "1") (pinfunction "GPB0_1") (pintype "bidirectional"))
      (node (ref "R51") (pin "1") (pinfunction "1_1") (pintype "passive"))
      (node (ref "S8") (pin "B") (pinfunction "B_B") (pintype "bidirectional"))
    )
    (net (code "32") (name "GPB0_41") (class "Default")
      (node (ref "CON_TFT_EXT") (pin "11") (pinfunction "11_11") (pintype "passive"))
      (node (ref "MCP_101") (pin "1") (pinfunction "GPB0_1") (pintype "bidirectional"))
    )
    (net (code "33") (name "GPB0_42") (class "Default")
      (node (ref "MCP_110") (pin "1") (pinfunction "GPB0_1") (pintype "bidirectional"))
      (node (ref "R14") (pin "1") (pinfunction "1_1") (pintype "passive"))
      (node (ref "S4") (pin "B") (pinfunction "B_B") (pintype "bidirectional"))
    )
    (net (code "34") (name "GPB1_5") (class "Default")
      (node (ref "MCP_111") (pin "2") (pinfunction "GPB1_2") (pintype "bidirectional"))
      (node (ref "R50") (pin "1") (pinfunction "1_1") (pintype "passive"))
      (node (ref "S8") (pin "A") (pinfunction "A_A") (pintype "bidirectional"))
    )
    (net (code "35") (name "GPB1_41") (class "Default")
      (node (ref "CON_TFT_EXT") (pin "12") (pinfunction "12_12") (pintype "passive"))
      (node (ref "MCP_101") (pin "2") (pinfunction "GPB1_2") (pintype "bidirectional"))
    )
    (net (code "36") (name "GPB1_42") (class "Default")
      (node (ref "MCP_110") (pin "2") (pinfunction "GPB1_2") (pintype "bidirectional"))
      (node (ref "R13") (pin "1") (pinfunction "1_1") (pintype "passive"))
      (node (ref "S4") (pin "A") (pinfunction "A_A") (pintype "bidirectional"))
    )
    (net (code "37") (name "GPB2_5") (class "Default")
      (node (ref "MCP_111") (pin "3") (pinfunction "GPB2_3") (pintype "bidirectional"))
      (node (ref "R64") (pin "1") (pinfunction "1_1") (pintype "passive"))
      (node (ref "R75") (pin "1") (pinfunction "1_1") (pintype "passive"))
      (node (ref "S7") (pin "3") (pinfunction "SW_3") (pintype "passive"))
    )
    (net (code "38") (name "GPB2_41") (class "Default")
      (node (ref "CON_TFT_EXT") (pin "10") (pinfunction "10_10") (pintype "passive"))
      (node (ref "MCP_101") (pin "3") (pinfunction "GPB2_3") (pintype "bidirectional"))
    )
    (net (code "39") (name "GPB2_42") (class "Default")
      (node (ref "MCP_110") (pin "3") (pinfunction "GPB2_3") (pintype "bidirectional"))
      (node (ref "R16") (pin "1") (pinfunction "1_1") (pintype "passive"))
      (node (ref "S5") (pin "B") (pinfunction "B_B") (pintype "bidirectional"))
    )
    (net (code "40") (name "GPB3_5") (class "Default")
      (node (ref "MCP_111") (pin "4") (pinfunction "GPB3_4") (pintype "bidirectional"))
      (node (ref "R48") (pin "1") (pinfunction "1_1") (pintype "passive"))
      (node (ref "S7") (pin "A") (pinfunction "A_A") (pintype "bidirectional"))
    )
    (net (code "41") (name "GPB3_41") (class "Default")
      (node (ref "CON_TFT_EXT") (pin "8") (pinfunction "8_8") (pintype "passive"))
      (node (ref "MCP_101") (pin "4") (pinfunction "GPB3_4") (pintype "bidirectional"))
    )
    (net (code "42") (name "GPB3_42") (class "Default")
      (node (ref "MCP_110") (pin "4") (pinfunction "GPB3_4") (pintype "bidirectional"))
      (node (ref "R15") (pin "1") (pinfunction "1_1") (pintype "passive"))
      (node (ref "S5") (pin "A") (pinfunction "A_A") (pintype "bidirectional"))
    )
    (net (code "43") (name "GPB4_5") (class "Default")
      (node (ref "MCP_111") (pin "5") (pinfunction "GPB4_5") (pintype "bidirectional"))
      (node (ref "R49") (pin "1") (pinfunction "1_1") (pintype "passive"))
      (node (ref "S7") (pin "B") (pinfunction "B_B") (pintype "bidirectional"))
    )
    (net (code "44") (name "GPB4_41") (class "Default")
      (node (ref "CON_TFT_EXT") (pin "6") (pinfunction "6_6") (pintype "passive"))
      (node (ref "MCP_101") (pin "5") (pinfunction "GPB4_5") (pintype "bidirectional"))
    )
    (net (code "45") (name "GPB4_42") (class "Default")
      (node (ref "MCP_110") (pin "5") (pinfunction "GPB4_5") (pintype "bidirectional"))
      (node (ref "R22") (pin "1") (pinfunction "1_1") (pintype "passive"))
      (node (ref "R39") (pin "1") (pinfunction "1_1") (pintype "passive"))
      (node (ref "S5") (pin "3") (pinfunction "SW_3") (pintype "passive"))
    )
    (net (code "46") (name "GPB5_5") (class "Default")
      (node (ref "MCP_111") (pin "6") (pinfunction "GPB5_6") (pintype "bidirectional"))
      (node (ref "R19") (pin "1") (pinfunction "1_1") (pintype "passive"))
      (node (ref "R27") (pin "1") (pinfunction "1_1") (pintype "passive"))
      (node (ref "S2") (pin "3") (pinfunction "SW_3") (pintype "passive"))
    )
    (net (code "47") (name "GPB5_41") (class "Default")
      (node (ref "CON_TFT_EXT") (pin "4") (pinfunction "4_4") (pintype "passive"))
      (node (ref "MCP_101") (pin "6") (pinfunction "GPB5_6") (pintype "bidirectional"))
    )
    (net (code "48") (name "GPB5_42") (class "Default")
      (node (ref "MCP_110") (pin "6") (pinfunction "GPB5_6") (pintype "bidirectional"))
      (node (ref "R18") (pin "1") (pinfunction "1_1") (pintype "passive"))
      (node (ref "S6") (pin "B") (pinfunction "B_B") (pintype "bidirectional"))
    )
    (net (code "49") (name "GPB6_5") (class "Default")
      (node (ref "MCP_111") (pin "7") (pinfunction "GPB6_7") (pintype "bidirectional"))
      (node (ref "R9") (pin "1") (pinfunction "1_1") (pintype "passive"))
      (node (ref "S2") (pin "A") (pinfunction "A_A") (pintype "bidirectional"))
    )
    (net (code "50") (name "GPB6_41") (class "Default")
      (node (ref "MCP_101") (pin "7") (pinfunction "GPB6_7") (pintype "bidirectional"))
      (node (ref "R62") (pin "1") (pinfunction "1_1") (pintype "passive"))
      (node (ref "S14") (pin "A") (pinfunction "A_A") (pintype "bidirectional"))
    )
    (net (code "51") (name "GPB6_42") (class "Default")
      (node (ref "MCP_110") (pin "7") (pinfunction "GPB6_7") (pintype "bidirectional"))
      (node (ref "R17") (pin "1") (pinfunction "1_1") (pintype "passive"))
      (node (ref "S6") (pin "A") (pinfunction "A_A") (pintype "bidirectional"))
    )
    (net (code "52") (name "GPB7_5") (class "Default")
      (node (ref "MCP_111") (pin "8") (pinfunction "GPB7_8") (pintype "bidirectional"))
      (node (ref "R10") (pin "1") (pinfunction "1_1") (pintype "passive"))
      (node (ref "S2") (pin "B") (pinfunction "B_B") (pintype "bidirectional"))
    )
    (net (code "53") (name "GPB7_41") (class "Default")
      (node (ref "MCP_101") (pin "8") (pinfunction "GPB7_8") (pintype "bidirectional"))
      (node (ref "R63") (pin "1") (pinfunction "1_1") (pintype "passive"))
      (node (ref "S14") (pin "B") (pinfunction "B_B") (pintype "bidirectional"))
    )
    (net (code "54") (name "GPB7_42") (class "Default")
      (node (ref "MCP_110") (pin "8") (pinfunction "GPB7_8") (pintype "bidirectional"))
      (node (ref "R23") (pin "1") (pinfunction "1_1") (pintype "passive"))
      (node (ref "R43") (pin "1") (pinfunction "1_1") (pintype "passive"))
      (node (ref "S6") (pin "3") (pinfunction "SW_3") (pintype "passive"))
    )
    (net (code "55") (name "GPIO_EXTI0") (class "Default")
      (node (ref "F446") (pin "5") (pinfunction "PH0-OSC_IN_5") (pintype "bidirectional"))
      (node (ref "MCP_101") (pin "19") (pinfunction "INTB_19") (pintype "bidirectional"))
    )
    (net (code "56") (name "GPIO_EXTI1") (class "Default")
      (node (ref "CON_STH_BRD") (pin "17") (pinfunction "17_17") (pintype "passive"))
      (node (ref "F446") (pin "27") (pinfunction "PB1_27") (pintype "bidirectional"))
    )
    (net (code "57") (name "GPIO_EXTI2") (class "Default")
      (node (ref "F446") (pin "10") (pinfunction "PC2_10") (pintype "bidirectional"))
      (node (ref "MCP_110") (pin "19") (pinfunction "INTB_19") (pintype "bidirectional"))
    )
    (net (code "58") (name "GPIO_EXTI3") (class "Default")
      (node (ref "F446") (pin "11") (pinfunction "PC3_11") (pintype "bidirectional"))
      (node (ref "MCP_110") (pin "20") (pinfunction "INTA_20") (pintype "bidirectional"))
    )
    (net (code "59") (name "GPIO_EXTI4") (class "Default")
      (node (ref "F446") (pin "24") (pinfunction "PC4_24") (pintype "bidirectional"))
      (node (ref "MCP_111") (pin "20") (pinfunction "INTA_20") (pintype "bidirectional"))
    )
    (net (code "60") (name "GPIO_EXTI5") (class "Default")
      (node (ref "F446") (pin "25") (pinfunction "PC5_25") (pintype "bidirectional"))
      (node (ref "MCP_111") (pin "19") (pinfunction "INTB_19") (pintype "bidirectional"))
    )
    (net (code "61") (name "GPIO_EXTI6") (class "Default")
      (node (ref "CON_STH_BRD") (pin "16") (pinfunction "16_16") (pintype "passive"))
      (node (ref "F446") (pin "37") (pinfunction "PC6_37") (pintype "bidirectional"))
    )
    (net (code "62") (name "GPIO_EXTI7") (class "Default")
      (node (ref "CON_STH_BRD") (pin "13") (pinfunction "13_13") (pintype "passive"))
      (node (ref "F446") (pin "38") (pinfunction "PC7_38") (pintype "bidirectional"))
    )
    (net (code "63") (name "GPIO_EXTI8") (class "Default")
      (node (ref "CON_STH_BRD") (pin "14") (pinfunction "14_14") (pintype "passive"))
      (node (ref "F446") (pin "39") (pinfunction "PC8_39") (pintype "bidirectional"))
    )
    (net (code "64") (name "GPIO_EXTI9") (class "Default")
      (node (ref "CON_STH_BRD") (pin "9") (pinfunction "9_9") (pintype "passive"))
      (node (ref "F446") (pin "42") (pinfunction "PA9_42") (pintype "bidirectional"))
    )
    (net (code "65") (name "GPIO_EXTI10") (class "Default")
      (node (ref "CON_STH_BRD") (pin "10") (pinfunction "10_10") (pintype "passive"))
      (node (ref "F446") (pin "43") (pinfunction "PA10_43") (pintype "bidirectional"))
    )
    (net (code "66") (name "GPIO_EXTI11") (class "Default")
      (node (ref "CON_STH_BRD") (pin "7") (pinfunction "7_7") (pintype "passive"))
      (node (ref "F446") (pin "44") (pinfunction "PA11_44") (pintype "bidirectional"))
    )
    (net (code "67") (name "GPIO_EXTI12") (class "Default")
      (node (ref "CON_STH_BRD") (pin "8") (pinfunction "8_8") (pintype "passive"))
      (node (ref "F446") (pin "45") (pinfunction "PA12_45") (pintype "bidirectional"))
    )
    (net (code "68") (name "GPIO_EXTI13") (class "Default")
      (node (ref "F446") (pin "2") (pinfunction "PC13_2") (pintype "bidirectional"))
      (node (ref "MCP_101") (pin "20") (pinfunction "INTA_20") (pintype "bidirectional"))
    )
    (net (code "69") (name "GPIO_EXTI14") (class "Default")
      (node (ref "CON_STH_BRD") (pin "18") (pinfunction "18_18") (pintype "passive"))
      (node (ref "F446") (pin "35") (pinfunction "PB14_35") (pintype "bidirectional"))
    )
    (net (code "70") (name "GPIO_EXTI15") (class "Default")
      (node (ref "CON_STH_BRD") (pin "15") (pinfunction "15_15") (pintype "passive"))
      (node (ref "F446") (pin "36") (pinfunction "PB15_36") (pintype "bidirectional"))
    )
    (net (code "71") (name "I2C1_SCL") (class "Default")
      (node (ref "F446") (pin "61") (pinfunction "PB8_61") (pintype "bidirectional"))
      (node (ref "MCP_101") (pin "12") (pinfunction "SCL_12") (pintype "bidirectional"))
      (node (ref "MCP_110") (pin "12") (pinfunction "SCL_12") (pintype "bidirectional"))
      (node (ref "MCP_111") (pin "12") (pinfunction "SCL_12") (pintype "bidirectional"))
      (node (ref "R45") (pin "1") (pinfunction "1_1") (pintype "passive"))
      (node (ref "R47") (pin "1") (pinfunction "1_1") (pintype "passive"))
      (node (ref "R8") (pin "1") (pinfunction "1_1") (pintype "passive"))
    )
    (net (code "72") (name "I2C1_SDA") (class "Default")
      (node (ref "F446") (pin "62") (pinfunction "PB9_62") (pintype "bidirectional"))
      (node (ref "MCP_101") (pin "13") (pinfunction "SDA_13") (pintype "bidirectional"))
      (node (ref "MCP_110") (pin "13") (pinfunction "SDA_13") (pintype "bidirectional"))
      (node (ref "MCP_111") (pin "13") (pinfunction "SDA_13") (pintype "bidirectional"))
      (node (ref "R44") (pin "1") (pinfunction "1_1") (pintype "passive"))
      (node (ref "R46") (pin "1") (pinfunction "1_1") (pintype "passive"))
      (node (ref "R7") (pin "1") (pinfunction "1_1") (pintype "passive"))
    )
    (net (code "73") (name "I2C2_SCL") (class "Default")
      (node (ref "CON_STH_BRD") (pin "20") (pinfunction "20_20") (pintype "passive"))
      (node (ref "F446") (pin "29") (pinfunction "PB10_29") (pintype "bidirectional"))
    )
    (net (code "74") (name "I2C2_SDA") (class "Default")
      (node (ref "CON_STH_BRD") (pin "5") (pinfunction "5_5") (pintype "passive"))
      (node (ref "F446") (pin "53") (pinfunction "PC12_53") (pintype "bidirectional"))
    )
    (net (code "75") (name "I2C3_SCL") (class "Default")
      (node (ref "CON_STH_BRD") (pin "12") (pinfunction "12_12") (pintype "passive"))
      (node (ref "F446") (pin "41") (pinfunction "PA8_41") (pintype "bidirectional"))
    )
    (net (code "76") (name "I2C3_SDA") (class "Default")
      (node (ref "CON_STH_BRD") (pin "11") (pinfunction "11_11") (pintype "passive"))
      (node (ref "F446") (pin "40") (pinfunction "PC9_40") (pintype "bidirectional"))
    )
    (net (code "77") (name "NRST") (class "Default")
      (node (ref "C1") (pin "2") (pinfunction "2_2") (pintype "passive"))
      (node (ref "F446") (pin "7") (pinfunction "NRST_7") (pintype "bidirectional"))
      (node (ref "NRST") (pin "2") (pinfunction "2_2") (pintype "bidirectional"))
      (node (ref "R2") (pin "2") (pinfunction "2_2") (pintype "passive"))
      (node (ref "STLINK") (pin "3") (pinfunction "3_3") (pintype "passive"))
    )
    (net (code "78") (name "Net-(C19-Pad2)") (class "Default")
      (node (ref "C19") (pin "2") (pinfunction "2_2") (pintype "passive"))
      (node (ref "R9") (pin "2") (pinfunction "2_2") (pintype "passive"))
    )
    (net (code "79") (name "Net-(C20-Pad2)") (class "Default")
      (node (ref "C20") (pin "2") (pinfunction "2_2") (pintype "passive"))
      (node (ref "R10") (pin "2") (pinfunction "2_2") (pintype "passive"))
    )
    (net (code "80") (name "Net-(C21-Pad2)") (class "Default")
      (node (ref "C21") (pin "2") (pinfunction "2_2") (pintype "passive"))
      (node (ref "R11") (pin "2") (pinfunction "2_2") (pintype "passive"))
    )
    (net (code "81") (name "Net-(C22-Pad2)") (class "Default")
      (node (ref "C22") (pin "2") (pinfunction "2_2") (pintype "passive"))
      (node (ref "R12") (pin "2") (pinfunction "2_2") (pintype "passive"))
    )
    (net (code "82") (name "Net-(C23-Pad2)") (class "Default")
      (node (ref "C23") (pin "2") (pinfunction "2_2") (pintype "passive"))
      (node (ref "R13") (pin "2") (pinfunction "2_2") (pintype "passive"))
    )
    (net (code "83") (name "Net-(C24-Pad2)") (class "Default")
      (node (ref "C24") (pin "2") (pinfunction "2_2") (pintype "passive"))
      (node (ref "R14") (pin "2") (pinfunction "2_2") (pintype "passive"))
    )
    (net (code "84") (name "Net-(C25-Pad2)") (class "Default")
      (node (ref "C25") (pin "2") (pinfunction "2_2") (pintype "passive"))
      (node (ref "R15") (pin "2") (pinfunction "2_2") (pintype "passive"))
    )
    (net (code "85") (name "Net-(C26-Pad2)") (class "Default")
      (node (ref "C26") (pin "2") (pinfunction "2_2") (pintype "passive"))
      (node (ref "R16") (pin "2") (pinfunction "2_2") (pintype "passive"))
    )
    (net (code "86") (name "Net-(C27-Pad2)") (class "Default")
      (node (ref "C27") (pin "2") (pinfunction "2_2") (pintype "passive"))
      (node (ref "R17") (pin "2") (pinfunction "2_2") (pintype "passive"))
    )
    (net (code "87") (name "Net-(C28-Pad2)") (class "Default")
      (node (ref "C28") (pin "2") (pinfunction "2_2") (pintype "passive"))
      (node (ref "R18") (pin "2") (pinfunction "2_2") (pintype "passive"))
    )
    (net (code "88") (name "Net-(C34-Pad1)") (class "Default")
      (node (ref "C34") (pin "1") (pinfunction "1_1") (pintype "passive"))
      (node (ref "R19") (pin "2") (pinfunction "2_2") (pintype "passive"))
    )
    (net (code "89") (name "Net-(C35-Pad1)") (class "Default")
      (node (ref "C35") (pin "1") (pinfunction "1_1") (pintype "passive"))
      (node (ref "R20") (pin "2") (pinfunction "2_2") (pintype "passive"))
    )
    (net (code "90") (name "Net-(C36-Pad1)") (class "Default")
      (node (ref "C36") (pin "1") (pinfunction "1_1") (pintype "passive"))
      (node (ref "R21") (pin "2") (pinfunction "2_2") (pintype "passive"))
    )
    (net (code "91") (name "Net-(C37-Pad1)") (class "Default")
      (node (ref "C37") (pin "1") (pinfunction "1_1") (pintype "passive"))
      (node (ref "R22") (pin "2") (pinfunction "2_2") (pintype "passive"))
    )
    (net (code "92") (name "Net-(C38-Pad1)") (class "Default")
      (node (ref "C38") (pin "1") (pinfunction "1_1") (pintype "passive"))
      (node (ref "R23") (pin "2") (pinfunction "2_2") (pintype "passive"))
    )
    (net (code "93") (name "Net-(C51-Pad2)") (class "Default")
      (node (ref "C51") (pin "2") (pinfunction "2_2") (pintype "passive"))
      (node (ref "R48") (pin "2") (pinfunction "2_2") (pintype "passive"))
    )
    (net (code "94") (name "Net-(C52-Pad2)") (class "Default")
      (node (ref "C52") (pin "2") (pinfunction "2_2") (pintype "passive"))
      (node (ref "R49") (pin "2") (pinfunction "2_2") (pintype "passive"))
    )
    (net (code "95") (name "Net-(C53-Pad2)") (class "Default")
      (node (ref "C53") (pin "2") (pinfunction "2_2") (pintype "passive"))
      (node (ref "R50") (pin "2") (pinfunction "2_2") (pintype "passive"))
    )
    (net (code "96") (name "Net-(C54-Pad2)") (class "Default")
      (node (ref "C54") (pin "2") (pinfunction "2_2") (pintype "passive"))
      (node (ref "R51") (pin "2") (pinfunction "2_2") (pintype "passive"))
    )
    (net (code "97") (name "Net-(C55-Pad2)") (class "Default")
      (node (ref "C55") (pin "2") (pinfunction "2_2") (pintype "passive"))
      (node (ref "R52") (pin "2") (pinfunction "2_2") (pintype "passive"))
    )
    (net (code "98") (name "Net-(C56-Pad2)") (class "Default")
      (node (ref "C56") (pin "2") (pinfunction "2_2") (pintype "passive"))
      (node (ref "R53") (pin "2") (pinfunction "2_2") (pintype "passive"))
    )
    (net (code "99") (name "Net-(C57-Pad2)") (class "Default")
      (node (ref "C57") (pin "2") (pinfunction "2_2") (pintype "passive"))
      (node (ref "R54") (pin "2") (pinfunction "2_2") (pintype "passive"))
    )
    (net (code "100") (name "Net-(C58-Pad2)") (class "Default")
      (node (ref "C58") (pin "2") (pinfunction "2_2") (pintype "passive"))
      (node (ref "R55") (pin "2") (pinfunction "2_2") (pintype "passive"))
    )
    (net (code "101") (name "Net-(C59-Pad2)") (class "Default")
      (node (ref "C59") (pin "2") (pinfunction "2_2") (pintype "passive"))
      (node (ref "R56") (pin "2") (pinfunction "2_2") (pintype "passive"))
    )
    (net (code "102") (name "Net-(C60-Pad2)") (class "Default")
      (node (ref "C60") (pin "2") (pinfunction "2_2") (pintype "passive"))
      (node (ref "R57") (pin "2") (pinfunction "2_2") (pintype "passive"))
    )
    (net (code "103") (name "Net-(C61-Pad2)") (class "Default")
      (node (ref "C61") (pin "2") (pinfunction "2_2") (pintype "passive"))
      (node (ref "R58") (pin "2") (pinfunction "2_2") (pintype "passive"))
    )
    (net (code "104") (name "Net-(C62-Pad2)") (class "Default")
      (node (ref "C62") (pin "2") (pinfunction "2_2") (pintype "passive"))
      (node (ref "R59") (pin "2") (pinfunction "2_2") (pintype "passive"))
    )
    (net (code "105") (name "Net-(C63-Pad2)") (class "Default")
      (node (ref "C63") (pin "2") (pinfunction "2_2") (pintype "passive"))
      (node (ref "R60") (pin "2") (pinfunction "2_2") (pintype "passive"))
    )
    (net (code "106") (name "Net-(C64-Pad2)") (class "Default")
      (node (ref "C64") (pin "2") (pinfunction "2_2") (pintype "passive"))
      (node (ref "R61") (pin "2") (pinfunction "2_2") (pintype "passive"))
    )
    (net (code "107") (name "Net-(C65-Pad2)") (class "Default")
      (node (ref "C65") (pin "2") (pinfunction "2_2") (pintype "passive"))
      (node (ref "R62") (pin "2") (pinfunction "2_2") (pintype "passive"))
    )
    (net (code "108") (name "Net-(C66-Pad2)") (class "Default")
      (node (ref "C66") (pin "2") (pinfunction "2_2") (pintype "passive"))
      (node (ref "R63") (pin "2") (pinfunction "2_2") (pintype "passive"))
    )
    (net (code "109") (name "Net-(C75-Pad1)") (class "Default")
      (node (ref "C75") (pin "1") (pinfunction "1_1") (pintype "passive"))
      (node (ref "R64") (pin "2") (pinfunction "2_2") (pintype "passive"))
    )
    (net (code "110") (name "Net-(C76-Pad1)") (class "Default")
      (node (ref "C76") (pin "1") (pinfunction "1_1") (pintype "passive"))
      (node (ref "R65") (pin "2") (pinfunction "2_2") (pintype "passive"))
    )
    (net (code "111") (name "Net-(C77-Pad1)") (class "Default")
      (node (ref "C77") (pin "1") (pinfunction "1_1") (pintype "passive"))
      (node (ref "R66") (pin "2") (pinfunction "2_2") (pintype "passive"))
    )
    (net (code "112") (name "Net-(C78-Pad1)") (class "Default")
      (node (ref "C78") (pin "1") (pinfunction "1_1") (pintype "passive"))
      (node (ref "R67") (pin "2") (pinfunction "2_2") (pintype "passive"))
    )
    (net (code "113") (name "Net-(C79-Pad1)") (class "Default")
      (node (ref "C79") (pin "1") (pinfunction "1_1") (pintype "passive"))
      (node (ref "R68") (pin "2") (pinfunction "2_2") (pintype "passive"))
    )
    (net (code "114") (name "Net-(C80-Pad1)") (class "Default")
      (node (ref "C80") (pin "1") (pinfunction "1_1") (pintype "passive"))
      (node (ref "R69") (pin "2") (pinfunction "2_2") (pintype "passive"))
    )
    (net (code "115") (name "Net-(C81-Pad1)") (class "Default")
      (node (ref "C81") (pin "1") (pinfunction "1_1") (pintype "passive"))
      (node (ref "R70") (pin "2") (pinfunction "2_2") (pintype "passive"))
    )
    (net (code "116") (name "Net-(C82-Pad1)") (class "Default")
      (node (ref "C82") (pin "1") (pinfunction "1_1") (pintype "passive"))
      (node (ref "R71") (pin "2") (pinfunction "2_2") (pintype "passive"))
    )
    (net (code "117") (name "Net-(F446-BOOT0)") (class "Default")
      (node (ref "F446") (pin "60") (pinfunction "BOOT0_60") (pintype "input"))
      (node (ref "R3") (pin "1") (pinfunction "1_1") (pintype "passive"))
    )
    (net (code "118") (name "Net-(F446-VCAP_1)") (class "Default")
      (node (ref "C2") (pin "2") (pinfunction "2_2") (pintype "passive"))
      (node (ref "F446") (pin "30") (pinfunction "VCAP_1_30") (pintype "power_in"))
    )
    (net (code "119") (name "Net-(L1-Pad1)") (class "Default")
      (node (ref "L1") (pin "1") (pinfunction "1_1") (pintype "passive"))
      (node (ref "R4") (pin "1") (pinfunction "1_1") (pintype "passive"))
    )
    (net (code "120") (name "Net-(LD_3V-PadA)") (class "Default")
      (node (ref "LD_3V") (pin "A") (pinfunction "A_A") (pintype "passive"))
      (node (ref "R5") (pin "2") (pinfunction "2_2") (pintype "passive"))
    )
    (net (code "121") (name "Net-(LD_5V-PadA)") (class "Default")
      (node (ref "LD_5V") (pin "A") (pinfunction "A_A") (pintype "passive"))
      (node (ref "R6") (pin "2") (pinfunction "2_2") (pintype "passive"))
    )
    (net (code "122") (name "Net-(LD_GR-PadA)") (class "Default")
      (node (ref "LD_GR") (pin "A") (pinfunction "A_A") (pintype "passive"))
      (node (ref "R1") (pin "2") (pinfunction "2_2") (pintype "passive"))
    )
    (net (code "123") (name "Net-(PX_BF-OUT0)") (class "Default")
      (node (ref "PX_BF") (pin "1") (pinfunction "OUT0_1") (pintype "bidirectional"))
      (node (ref "R76") (pin "1") (pinfunction "1_1") (pintype "passive"))
    )
    (net (code "124") (name "Net-(PX_BF-OUT1)") (class "Default")
      (node (ref "PX_BF") (pin "2") (pinfunction "OUT1_2") (pintype "bidirectional"))
      (node (ref "R77") (pin "1") (pinfunction "1_1") (pintype "passive"))
    )
    (net (code "125") (name "Net-(PX_BF-OUT2)") (class "Default")
      (node (ref "PX_BF") (pin "3") (pinfunction "OUT2_3") (pintype "bidirectional"))
      (node (ref "R78") (pin "1") (pinfunction "1_1") (pintype "passive"))
    )
    (net (code "126") (name "Net-(PX_CHORUS-OUT0)") (class "Default")
      (node (ref "PX_CHORUS") (pin "1") (pinfunction "OUT0_1") (pintype "bidirectional"))
      (node (ref "R36") (pin "1") (pinfunction "1_1") (pintype "passive"))
    )
    (net (code "127") (name "Net-(PX_CHORUS-OUT1)") (class "Default")
      (node (ref "PX_CHORUS") (pin "2") (pinfunction "OUT1_2") (pintype "bidirectional"))
      (node (ref "R37") (pin "1") (pinfunction "1_1") (pintype "passive"))
    )
    (net (code "128") (name "Net-(PX_CHORUS-OUT2)") (class "Default")
      (node (ref "PX_CHORUS") (pin "3") (pinfunction "OUT2_3") (pintype "bidirectional"))
      (node (ref "R38") (pin "1") (pinfunction "1_1") (pintype "passive"))
    )
    (net (code "129") (name "Net-(PX_DELAY-OUT0)") (class "Default")
      (node (ref "PX_DELAY") (pin "1") (pinfunction "OUT0_1") (pintype "bidirectional"))
      (node (ref "R32") (pin "1") (pinfunction "1_1") (pintype "passive"))
    )
    (net (code "130") (name "Net-(PX_DELAY-OUT1)") (class "Default")
      (node (ref "PX_DELAY") (pin "2") (pinfunction "OUT1_2") (pintype "bidirectional"))
      (node (ref "R33") (pin "1") (pinfunction "1_1") (pintype "passive"))
    )
    (net (code "131") (name "Net-(PX_DELAY-OUT2)") (class "Default")
      (node (ref "PX_DELAY") (pin "3") (pinfunction "OUT2_3") (pintype "bidirectional"))
      (node (ref "R34") (pin "1") (pinfunction "1_1") (pintype "passive"))
    )
    (net (code "132") (name "Net-(PX_DRIVE-OUT0)") (class "Default")
      (node (ref "PX_DRIVE") (pin "1") (pinfunction "OUT0_1") (pintype "bidirectional"))
      (node (ref "R40") (pin "1") (pinfunction "1_1") (pintype "passive"))
    )
    (net (code "133") (name "Net-(PX_DRIVE-OUT1)") (class "Default")
      (node (ref "PX_DRIVE") (pin "2") (pinfunction "OUT1_2") (pintype "bidirectional"))
      (node (ref "R41") (pin "1") (pinfunction "1_1") (pintype "passive"))
    )
    (net (code "134") (name "Net-(PX_DRIVE-OUT2)") (class "Default")
      (node (ref "PX_DRIVE") (pin "3") (pinfunction "OUT2_3") (pintype "bidirectional"))
      (node (ref "R42") (pin "1") (pinfunction "1_1") (pintype "passive"))
    )
    (net (code "135") (name "Net-(PX_HUMAN-OUT0)") (class "Default")
      (node (ref "PX_HUMAN") (pin "1") (pinfunction "OUT0_1") (pintype "bidirectional"))
      (node (ref "R88") (pin "1") (pinfunction "1_1") (pintype "passive"))
    )
    (net (code "136") (name "Net-(PX_HUMAN-OUT1)") (class "Default")
      (node (ref "PX_HUMAN") (pin "2") (pinfunction "OUT1_2") (pintype "bidirectional"))
      (node (ref "R89") (pin "1") (pinfunction "1_1") (pintype "passive"))
    )
    (net (code "137") (name "Net-(PX_HUMAN-OUT2)") (class "Default")
      (node (ref "PX_HUMAN") (pin "3") (pinfunction "OUT2_3") (pintype "bidirectional"))
      (node (ref "R90") (pin "1") (pinfunction "1_1") (pintype "passive"))
    )
    (net (code "138") (name "Net-(PX_LATCH-OUT0)") (class "Default")
      (node (ref "PX_LATCH") (pin "1") (pinfunction "OUT0_1") (pintype "bidirectional"))
      (node (ref "R80") (pin "1") (pinfunction "1_1") (pintype "passive"))
    )
    (net (code "139") (name "Net-(PX_LATCH-OUT1)") (class "Default")
      (node (ref "PX_LATCH") (pin "2") (pinfunction "OUT1_2") (pintype "bidirectional"))
      (node (ref "R81") (pin "1") (pinfunction "1_1") (pintype "passive"))
    )
    (net (code "140") (name "Net-(PX_LATCH-OUT2)") (class "Default")
      (node (ref "PX_LATCH") (pin "3") (pinfunction "OUT2_3") (pintype "bidirectional"))
      (node (ref "R82") (pin "1") (pinfunction "1_1") (pintype "passive"))
    )
    (net (code "141") (name "Net-(PX_ONOFF-OUT0)") (class "Default")
      (node (ref "PX_ONOFF") (pin "1") (pinfunction "OUT0_1") (pintype "bidirectional"))
      (node (ref "R72") (pin "1") (pinfunction "1_1") (pintype "passive"))
    )
    (net (code "142") (name "Net-(PX_ONOFF-OUT1)") (class "Default")
      (node (ref "PX_ONOFF") (pin "2") (pinfunction "OUT1_2") (pintype "bidirectional"))
      (node (ref "R73") (pin "1") (pinfunction "1_1") (pintype "passive"))
    )
    (net (code "143") (name "Net-(PX_ONOFF-OUT2)") (class "Default")
      (node (ref "PX_ONOFF") (pin "3") (pinfunction "OUT2_3") (pintype "bidirectional"))
      (node (ref "R74") (pin "1") (pinfunction "1_1") (pintype "passive"))
    )
    (net (code "144") (name "Net-(PX_PATTERN-OUT0)") (class "Default")
      (node (ref "PX_PATTERN") (pin "1") (pinfunction "OUT0_1") (pintype "bidirectional"))
      (node (ref "R84") (pin "1") (pinfunction "1_1") (pintype "passive"))
    )
    (net (code "145") (name "Net-(PX_PATTERN-OUT1)") (class "Default")
      (node (ref "PX_PATTERN") (pin "2") (pinfunction "OUT1_2") (pintype "bidirectional"))
      (node (ref "R85") (pin "1") (pinfunction "1_1") (pintype "passive"))
    )
    (net (code "146") (name "Net-(PX_PATTERN-OUT2)") (class "Default")
      (node (ref "PX_PATTERN") (pin "3") (pinfunction "OUT2_3") (pintype "bidirectional"))
      (node (ref "R86") (pin "1") (pinfunction "1_1") (pintype "passive"))
    )
    (net (code "147") (name "Net-(PX_PORTA-OUT0)") (class "Default")
      (node (ref "PX_PORTA") (pin "1") (pinfunction "OUT0_1") (pintype "bidirectional"))
      (node (ref "R24") (pin "1") (pinfunction "1_1") (pintype "passive"))
    )
    (net (code "148") (name "Net-(PX_PORTA-OUT1)") (class "Default")
      (node (ref "PX_PORTA") (pin "2") (pinfunction "OUT1_2") (pintype "bidirectional"))
      (node (ref "R25") (pin "1") (pinfunction "1_1") (pintype "passive"))
    )
    (net (code "149") (name "Net-(PX_PORTA-OUT2)") (class "Default")
      (node (ref "PX_PORTA") (pin "3") (pinfunction "OUT2_3") (pintype "bidirectional"))
      (node (ref "R26") (pin "1") (pinfunction "1_1") (pintype "passive"))
    )
    (net (code "150") (name "Net-(PX_RANGE-OUT0)") (class "Default")
      (node (ref "PX_RANGE") (pin "1") (pinfunction "OUT0_1") (pintype "bidirectional"))
      (node (ref "R92") (pin "1") (pinfunction "1_1") (pintype "passive"))
    )
    (net (code "151") (name "Net-(PX_RANGE-OUT1)") (class "Default")
      (node (ref "PX_RANGE") (pin "2") (pinfunction "OUT1_2") (pintype "bidirectional"))
      (node (ref "R93") (pin "1") (pinfunction "1_1") (pintype "passive"))
    )
    (net (code "152") (name "Net-(PX_RANGE-OUT2)") (class "Default")
      (node (ref "PX_RANGE") (pin "3") (pinfunction "OUT2_3") (pintype "bidirectional"))
      (node (ref "R94") (pin "1") (pinfunction "1_1") (pintype "passive"))
    )
    (net (code "153") (name "Net-(PX_RATE-OUT0)") (class "Default")
      (node (ref "PX_RATE") (pin "1") (pinfunction "OUT0_1") (pintype "bidirectional"))
      (node (ref "R100") (pin "1") (pinfunction "1_1") (pintype "passive"))
    )
    (net (code "154") (name "Net-(PX_RATE-OUT1)") (class "Default")
      (node (ref "PX_RATE") (pin "2") (pinfunction "OUT1_2") (pintype "bidirectional"))
      (node (ref "R101") (pin "1") (pinfunction "1_1") (pintype "passive"))
    )
    (net (code "155") (name "Net-(PX_RATE-OUT2)") (class "Default")
      (node (ref "PX_RATE") (pin "3") (pinfunction "OUT2_3") (pintype "bidirectional"))
      (node (ref "R102") (pin "1") (pinfunction "1_1") (pintype "passive"))
    )
    (net (code "156") (name "Net-(PX_REVERB-OUT0)") (class "Default")
      (node (ref "PX_REVERB") (pin "1") (pinfunction "OUT0_1") (pintype "bidirectional"))
      (node (ref "R28") (pin "1") (pinfunction "1_1") (pintype "passive"))
    )
    (net (code "157") (name "Net-(PX_REVERB-OUT1)") (class "Default")
      (node (ref "PX_REVERB") (pin "2") (pinfunction "OUT1_2") (pintype "bidirectional"))
      (node (ref "R29") (pin "1") (pinfunction "1_1") (pintype "passive"))
    )
    (net (code "158") (name "Net-(PX_REVERB-OUT2)") (class "Default")
      (node (ref "PX_REVERB") (pin "3") (pinfunction "OUT2_3") (pintype "bidirectional"))
      (node (ref "R30") (pin "1") (pinfunction "1_1") (pintype "passive"))
    )
    (net (code "159") (name "Net-(PX_SYNC-OUT0)") (class "Default")
      (node (ref "PX_SYNC") (pin "1") (pinfunction "OUT0_1") (pintype "bidirectional"))
      (node (ref "R96") (pin "1") (pinfunction "1_1") (pintype "passive"))
    )
    (net (code "160") (name "Net-(PX_SYNC-OUT1)") (class "Default")
      (node (ref "PX_SYNC") (pin "2") (pinfunction "OUT1_2") (pintype "bidirectional"))
      (node (ref "R97") (pin "1") (pinfunction "1_1") (pintype "passive"))
    )
    (net (code "161") (name "Net-(PX_SYNC-OUT2)") (class "Default")
      (node (ref "PX_SYNC") (pin "3") (pinfunction "OUT2_3") (pintype "bidirectional"))
      (node (ref "R98") (pin "1") (pinfunction "1_1") (pintype "passive"))
    )
    (net (code "162") (name "Net-(REG-OUT)") (class "Default")
      (node (ref "R4") (pin "2") (pinfunction "2_2") (pintype "passive"))
      (node (ref "REG") (pin "5") (pinfunction "OUT_5") (pintype "output"))
    )
    (net (code "163") (name "Net-(S2--B)") (class "Default")
      (node (ref "R26") (pin "2") (pinfunction "2_2") (pintype "passive"))
      (node (ref "S2") (pin "4") (pinfunction "-B_4") (pintype "passive"))
    )
    (net (code "164") (name "Net-(S2--G)") (class "Default")
      (node (ref "R25") (pin "2") (pinfunction "2_2") (pintype "passive"))
      (node (ref "S2") (pin "2") (pinfunction "-G_2") (pintype "passive"))
    )
    (net (code "165") (name "Net-(S2--R)") (class "Default")
      (node (ref "R24") (pin "2") (pinfunction "2_2") (pintype "passive"))
      (node (ref "S2") (pin "1") (pinfunction "-R_1") (pintype "passive"))
    )
    (net (code "166") (name "Net-(S3--B)") (class "Default")
      (node (ref "R30") (pin "2") (pinfunction "2_2") (pintype "passive"))
      (node (ref "S3") (pin "4") (pinfunction "-B_4") (pintype "passive"))
    )
    (net (code "167") (name "Net-(S3--G)") (class "Default")
      (node (ref "R29") (pin "2") (pinfunction "2_2") (pintype "passive"))
      (node (ref "S3") (pin "2") (pinfunction "-G_2") (pintype "passive"))
    )
    (net (code "168") (name "Net-(S3--R)") (class "Default")
      (node (ref "R28") (pin "2") (pinfunction "2_2") (pintype "passive"))
      (node (ref "S3") (pin "1") (pinfunction "-R_1") (pintype "passive"))
    )
    (net (code "169") (name "Net-(S4--B)") (class "Default")
      (node (ref "R34") (pin "2") (pinfunction "2_2") (pintype "passive"))
      (node (ref "S4") (pin "4") (pinfunction "-B_4") (pintype "passive"))
    )
    (net (code "170") (name "Net-(S4--G)") (class "Default")
      (node (ref "R33") (pin "2") (pinfunction "2_2") (pintype "passive"))
      (node (ref "S4") (pin "2") (pinfunction "-G_2") (pintype "passive"))
    )
    (net (code "171") (name "Net-(S4--R)") (class "Default")
      (node (ref "R32") (pin "2") (pinfunction "2_2") (pintype "passive"))
      (node (ref "S4") (pin "1") (pinfunction "-R_1") (pintype "passive"))
    )
    (net (code "172") (name "Net-(S5--B)") (class "Default")
      (node (ref "R38") (pin "2") (pinfunction "2_2") (pintype "passive"))
      (node (ref "S5") (pin "4") (pinfunction "-B_4") (pintype "passive"))
    )
    (net (code "173") (name "Net-(S5--G)") (class "Default")
      (node (ref "R37") (pin "2") (pinfunction "2_2") (pintype "passive"))
      (node (ref "S5") (pin "2") (pinfunction "-G_2") (pintype "passive"))
    )
    (net (code "174") (name "Net-(S5--R)") (class "Default")
      (node (ref "R36") (pin "2") (pinfunction "2_2") (pintype "passive"))
      (node (ref "S5") (pin "1") (pinfunction "-R_1") (pintype "passive"))
    )
    (net (code "175") (name "Net-(S6--B)") (class "Default")
      (node (ref "R42") (pin "2") (pinfunction "2_2") (pintype "passive"))
      (node (ref "S6") (pin "4") (pinfunction "-B_4") (pintype "passive"))
    )
    (net (code "176") (name "Net-(S6--G)") (class "Default")
      (node (ref "R41") (pin "2") (pinfunction "2_2") (pintype "passive"))
      (node (ref "S6") (pin "2") (pinfunction "-G_2") (pintype "passive"))
    )
    (net (code "177") (name "Net-(S6--R)") (class "Default")
      (node (ref "R40") (pin "2") (pinfunction "2_2") (pintype "passive"))
      (node (ref "S6") (pin "1") (pinfunction "-R_1") (pintype "passive"))
    )
    (net (code "178") (name "Net-(S7--B)") (class "Default")
      (node (ref "R74") (pin "2") (pinfunction "2_2") (pintype "passive"))
      (node (ref "S7") (pin "4") (pinfunction "-B_4") (pintype "passive"))
    )
    (net (code "179") (name "Net-(S7--G)") (class "Default")
      (node (ref "R73") (pin "2") (pinfunction "2_2") (pintype "passive"))
      (node (ref "S7") (pin "2") (pinfunction "-G_2") (pintype "passive"))
    )
    (net (code "180") (name "Net-(S7--R)") (class "Default")
      (node (ref "R72") (pin "2") (pinfunction "2_2") (pintype "passive"))
      (node (ref "S7") (pin "1") (pinfunction "-R_1") (pintype "passive"))
    )
    (net (code "181") (name "Net-(S8--B)") (class "Default")
      (node (ref "R78") (pin "2") (pinfunction "2_2") (pintype "passive"))
      (node (ref "S8") (pin "4") (pinfunction "-B_4") (pintype "passive"))
    )
    (net (code "182") (name "Net-(S8--G)") (class "Default")
      (node (ref "R77") (pin "2") (pinfunction "2_2") (pintype "passive"))
      (node (ref "S8") (pin "2") (pinfunction "-G_2") (pintype "passive"))
    )
    (net (code "183") (name "Net-(S8--R)") (class "Default")
      (node (ref "R76") (pin "2") (pinfunction "2_2") (pintype "passive"))
      (node (ref "S8") (pin "1") (pinfunction "-R_1") (pintype "passive"))
    )
    (net (code "184") (name "Net-(S9--B)") (class "Default")
      (node (ref "R82") (pin "2") (pinfunction "2_2") (pintype "passive"))
      (node (ref "S9") (pin "4") (pinfunction "-B_4") (pintype "passive"))
    )
    (net (code "185") (name "Net-(S9--G)") (class "Default")
      (node (ref "R81") (pin "2") (pinfunction "2_2") (pintype "passive"))
      (node (ref "S9") (pin "2") (pinfunction "-G_2") (pintype "passive"))
    )
    (net (code "186") (name "Net-(S9--R)") (class "Default")
      (node (ref "R80") (pin "2") (pinfunction "2_2") (pintype "passive"))
      (node (ref "S9") (pin "1") (pinfunction "-R_1") (pintype "passive"))
    )
    (net (code "187") (name "Net-(S10--B)") (class "Default")
      (node (ref "R86") (pin "2") (pinfunction "2_2") (pintype "passive"))
      (node (ref "S10") (pin "4") (pinfunction "-B_4") (pintype "passive"))
    )
    (net (code "188") (name "Net-(S10--G)") (class "Default")
      (node (ref "R85") (pin "2") (pinfunction "2_2") (pintype "passive"))
      (node (ref "S10") (pin "2") (pinfunction "-G_2") (pintype "passive"))
    )
    (net (code "189") (name "Net-(S10--R)") (class "Default")
      (node (ref "R84") (pin "2") (pinfunction "2_2") (pintype "passive"))
      (node (ref "S10") (pin "1") (pinfunction "-R_1") (pintype "passive"))
    )
    (net (code "190") (name "Net-(S11--B)") (class "Default")
      (node (ref "R90") (pin "2") (pinfunction "2_2") (pintype "passive"))
      (node (ref "S11") (pin "4") (pinfunction "-B_4") (pintype "passive"))
    )
    (net (code "191") (name "Net-(S11--G)") (class "Default")
      (node (ref "R89") (pin "2") (pinfunction "2_2") (pintype "passive"))
      (node (ref "S11") (pin "2") (pinfunction "-G_2") (pintype "passive"))
    )
    (net (code "192") (name "Net-(S11--R)") (class "Default")
      (node (ref "R88") (pin "2") (pinfunction "2_2") (pintype "passive"))
      (node (ref "S11") (pin "1") (pinfunction "-R_1") (pintype "passive"))
    )
    (net (code "193") (name "Net-(S12--B)") (class "Default")
      (node (ref "R94") (pin "2") (pinfunction "2_2") (pintype "passive"))
      (node (ref "S12") (pin "4") (pinfunction "-B_4") (pintype "passive"))
    )
    (net (code "194") (name "Net-(S12--G)") (class "Default")
      (node (ref "R93") (pin "2") (pinfunction "2_2") (pintype "passive"))
      (node (ref "S12") (pin "2") (pinfunction "-G_2") (pintype "passive"))
    )
    (net (code "195") (name "Net-(S12--R)") (class "Default")
      (node (ref "R92") (pin "2") (pinfunction "2_2") (pintype "passive"))
      (node (ref "S12") (pin "1") (pinfunction "-R_1") (pintype "passive"))
    )
    (net (code "196") (name "Net-(S13--B)") (class "Default")
      (node (ref "R98") (pin "2") (pinfunction "2_2") (pintype "passive"))
      (node (ref "S13") (pin "4") (pinfunction "-B_4") (pintype "passive"))
    )
    (net (code "197") (name "Net-(S13--G)") (class "Default")
      (node (ref "R97") (pin "2") (pinfunction "2_2") (pintype "passive"))
      (node (ref "S13") (pin "2") (pinfunction "-G_2") (pintype "passive"))
    )
    (net (code "198") (name "Net-(S13--R)") (class "Default")
      (node (ref "R96") (pin "2") (pinfunction "2_2") (pintype "passive"))
      (node (ref "S13") (pin "1") (pinfunction "-R_1") (pintype "passive"))
    )
    (net (code "199") (name "Net-(S14--B)") (class "Default")
      (node (ref "R102") (pin "2") (pinfunction "2_2") (pintype "passive"))
      (node (ref "S14") (pin "4") (pinfunction "-B_4") (pintype "passive"))
    )
    (net (code "200") (name "Net-(S14--G)") (class "Default")
      (node (ref "R101") (pin "2") (pinfunction "2_2") (pintype "passive"))
      (node (ref "S14") (pin "2") (pinfunction "-G_2") (pintype "passive"))
    )
    (net (code "201") (name "Net-(S14--R)") (class "Default")
      (node (ref "R100") (pin "2") (pinfunction "2_2") (pintype "passive"))
      (node (ref "S14") (pin "1") (pinfunction "-R_1") (pintype "passive"))
    )
    (net (code "202") (name "PIXEL_71") (class "Default")
      (node (ref "PX_CHORUS") (pin "6") (pinfunction "SDI_6") (pintype "bidirectional"))
      (node (ref "PX_DRIVE") (pin "5") (pinfunction "SDO_5") (pintype "bidirectional"))
    )
    (net (code "203") (name "PIXEL_72") (class "Default")
      (node (ref "PX_CHORUS") (pin "5") (pinfunction "SDO_5") (pintype "bidirectional"))
      (node (ref "PX_DELAY") (pin "6") (pinfunction "SDI_6") (pintype "bidirectional"))
    )
    (net (code "204") (name "PIXEL_73") (class "Default")
      (node (ref "PX_DELAY") (pin "5") (pinfunction "SDO_5") (pintype "bidirectional"))
      (node (ref "PX_REVERB") (pin "6") (pinfunction "SDI_6") (pintype "bidirectional"))
    )
    (net (code "205") (name "PIXEL_74") (class "Default")
      (node (ref "PX_PORTA") (pin "6") (pinfunction "SDI_6") (pintype "bidirectional"))
      (node (ref "PX_REVERB") (pin "5") (pinfunction "SDO_5") (pintype "bidirectional"))
    )
    (net (code "206") (name "PIXEL_75") (class "Default")
      (node (ref "PX_ONOFF") (pin "6") (pinfunction "SDI_6") (pintype "bidirectional"))
      (node (ref "PX_PORTA") (pin "5") (pinfunction "SDO_5") (pintype "bidirectional"))
    )
    (net (code "207") (name "PIXEL_81") (class "Default")
      (node (ref "CON_TFT_EXT") (pin "9") (pinfunction "9_9") (pintype "passive"))
      (node (ref "PX_RATE") (pin "5") (pinfunction "SDO_5") (pintype "bidirectional"))
    )
    (net (code "208") (name "PIXEL_82") (class "Default")
      (node (ref "PX_RATE") (pin "6") (pinfunction "SDI_6") (pintype "bidirectional"))
      (node (ref "PX_SYNC") (pin "5") (pinfunction "SDO_5") (pintype "bidirectional"))
    )
    (net (code "209") (name "PIXEL_83") (class "Default")
      (node (ref "PX_RANGE") (pin "5") (pinfunction "SDO_5") (pintype "bidirectional"))
      (node (ref "PX_SYNC") (pin "6") (pinfunction "SDI_6") (pintype "bidirectional"))
    )
    (net (code "210") (name "PIXEL_84") (class "Default")
      (node (ref "PX_HUMAN") (pin "5") (pinfunction "SDO_5") (pintype "bidirectional"))
      (node (ref "PX_RANGE") (pin "6") (pinfunction "SDI_6") (pintype "bidirectional"))
    )
    (net (code "211") (name "PIXEL_85") (class "Default")
      (node (ref "PX_HUMAN") (pin "6") (pinfunction "SDI_6") (pintype "bidirectional"))
      (node (ref "PX_PATTERN") (pin "5") (pinfunction "SDO_5") (pintype "bidirectional"))
    )
    (net (code "212") (name "PIXEL_86") (class "Default")
      (node (ref "PX_LATCH") (pin "5") (pinfunction "SDO_5") (pintype "bidirectional"))
      (node (ref "PX_PATTERN") (pin "6") (pinfunction "SDI_6") (pintype "bidirectional"))
    )
    (net (code "213") (name "PIXEL_87") (class "Default")
      (node (ref "PX_BF") (pin "5") (pinfunction "SDO_5") (pintype "bidirectional"))
      (node (ref "PX_LATCH") (pin "6") (pinfunction "SDI_6") (pintype "bidirectional"))
    )
    (net (code "214") (name "PIXEL_88") (class "Default")
      (node (ref "PX_BF") (pin "6") (pinfunction "SDI_6") (pintype "bidirectional"))
      (node (ref "PX_ONOFF") (pin "5") (pinfunction "SDO_5") (pintype "bidirectional"))
    )
    (net (code "215") (name "RST") (class "Default")
      (node (ref "CON_STH_BRD") (pin "3") (pinfunction "3_3") (pintype "passive"))
      (node (ref "F446") (pin "55") (pinfunction "PB3_55") (pintype "bidirectional"))
      (node (ref "MCP_101") (pin "18") (pinfunction "~{RESET}_18") (pintype "bidirectional"))
      (node (ref "MCP_110") (pin "18") (pinfunction "~{RESET}_18") (pintype "bidirectional"))
      (node (ref "MCP_111") (pin "18") (pinfunction "~{RESET}_18") (pintype "bidirectional"))
    )
    (net (code "216") (name "SPI1_MOSI") (class "Default")
      (node (ref "CON_STH_BRD") (pin "6") (pinfunction "6_6") (pintype "passive"))
      (node (ref "F446") (pin "23") (pinfunction "PA7_23") (pintype "bidirectional"))
    )
    (net (code "217") (name "SPI2_MOSI") (class "Default")
      (node (ref "F446") (pin "9") (pinfunction "PC1_9") (pintype "bidirectional"))
      (node (ref "PX_DRIVE") (pin "6") (pinfunction "SDI_6") (pintype "bidirectional"))
    )
    (net (code "218") (name "SPI3_MOSI") (class "Default")
      (node (ref "CON_STH_BRD") (pin "19") (pinfunction "19_19") (pintype "passive"))
      (node (ref "F446") (pin "26") (pinfunction "PB0_26") (pintype "bidirectional"))
    )
    (net (code "219") (name "SWCLK") (class "Default")
      (node (ref "F446") (pin "49") (pinfunction "PA14_49") (pintype "bidirectional"))
      (node (ref "STLINK") (pin "4") (pinfunction "4_4") (pintype "passive"))
    )
    (net (code "220") (name "SWDIO") (class "Default")
      (node (ref "F446") (pin "46") (pinfunction "PA13_46") (pintype "bidirectional"))
      (node (ref "STLINK") (pin "2") (pinfunction "2_2") (pintype "passive"))
    )
    (net (code "221") (name "TIM3_CH1") (class "Default")
      (node (ref "F446") (pin "22") (pinfunction "PA6_22") (pintype "bidirectional"))
      (node (ref "R1") (pin "1") (pinfunction "1_1") (pintype "passive"))
    )
    (net (code "222") (name "UART4_RX") (class "Default")
      (node (ref "ANALOG") (pin "2") (pinfunction "2_2") (pintype "passive"))
      (node (ref "F446") (pin "52") (pinfunction "PC11_52") (pintype "bidirectional"))
    )
    (net (code "223") (name "UART4_TX") (class "Default")
      (node (ref "ANALOG") (pin "3") (pinfunction "3_3") (pintype "passive"))
      (node (ref "F446") (pin "14") (pinfunction "PA0_14") (pintype "bidirectional"))
    )
    (net (code "224") (name "USART1_RX") (class "Default")
      (node (ref "DISCO") (pin "2") (pinfunction "2_2") (pintype "passive"))
      (node (ref "F446") (pin "59") (pinfunction "PB7_59") (pintype "bidirectional"))
    )
    (net (code "225") (name "USART1_TX") (class "Default")
      (node (ref "DISCO") (pin "3") (pinfunction "3_3") (pintype "passive"))
      (node (ref "F446") (pin "58") (pinfunction "PB6_58") (pintype "bidirectional"))
    )
    (net (code "226") (name "USART2_RX") (class "Default")
      (node (ref "F446") (pin "17") (pinfunction "PA3_17") (pintype "bidirectional"))
      (node (ref "MIDI") (pin "2") (pinfunction "2_2") (pintype "passive"))
    )
    (net (code "227") (name "USART2_TX") (class "Default")
      (node (ref "F446") (pin "16") (pinfunction "PA2_16") (pintype "bidirectional"))
      (node (ref "MIDI") (pin "3") (pinfunction "3_3") (pintype "passive"))
    )
    (net (code "228") (name "unconnected-(F446-PA5-Pad21)") (class "Default")
      (node (ref "F446") (pin "21") (pinfunction "PA5_21") (pintype "bidirectional"))
    )
    (net (code "229") (name "unconnected-(F446-PA15-Pad50)") (class "Default")
      (node (ref "F446") (pin "50") (pinfunction "PA15_50") (pintype "bidirectional"))
    )
    (net (code "230") (name "unconnected-(F446-PB2-Pad28)") (class "Default")
      (node (ref "F446") (pin "28") (pinfunction "PB2_28") (pintype "bidirectional"))
    )
    (net (code "231") (name "unconnected-(F446-PB4-Pad56)") (class "Default")
      (node (ref "F446") (pin "56") (pinfunction "PB4_56") (pintype "bidirectional"))
    )
    (net (code "232") (name "unconnected-(F446-PB5-Pad57)") (class "Default")
      (node (ref "F446") (pin "57") (pinfunction "PB5_57") (pintype "bidirectional"))
    )
    (net (code "233") (name "unconnected-(F446-PB12-Pad33)") (class "Default")
      (node (ref "F446") (pin "33") (pinfunction "PB12_33") (pintype "bidirectional"))
    )
    (net (code "234") (name "unconnected-(F446-PB13-Pad34)") (class "Default")
      (node (ref "F446") (pin "34") (pinfunction "PB13_34") (pintype "bidirectional"))
    )
    (net (code "235") (name "unconnected-(F446-PC10-Pad51)") (class "Default")
      (node (ref "F446") (pin "51") (pinfunction "PC10_51") (pintype "bidirectional"))
    )
    (net (code "236") (name "unconnected-(F446-PC14-OSC32_IN-Pad3)") (class "Default")
      (node (ref "F446") (pin "3") (pinfunction "PC14-OSC32_IN_3") (pintype "bidirectional"))
    )
    (net (code "237") (name "unconnected-(F446-PC15-OSC32_OUT-Pad4)") (class "Default")
      (node (ref "F446") (pin "4") (pinfunction "PC15-OSC32_OUT_4") (pintype "bidirectional"))
    )
    (net (code "238") (name "unconnected-(F446-PD2-Pad54)") (class "Default")
      (node (ref "F446") (pin "54") (pinfunction "PD2_54") (pintype "bidirectional"))
    )
    (net (code "239") (name "unconnected-(F446-PH1-OSC_OUT-Pad6)") (class "Default")
      (node (ref "F446") (pin "6") (pinfunction "PH1-OSC_OUT_6") (pintype "bidirectional"))
    )
    (net (code "240") (name "unconnected-(PX_BF-TEST-Pad7)") (class "Default")
      (node (ref "PX_BF") (pin "7") (pinfunction "TEST_7") (pintype "bidirectional"))
    )
    (net (code "241") (name "unconnected-(PX_CHORUS-TEST-Pad7)") (class "Default")
      (node (ref "PX_CHORUS") (pin "7") (pinfunction "TEST_7") (pintype "bidirectional"))
    )
    (net (code "242") (name "unconnected-(PX_DELAY-TEST-Pad7)") (class "Default")
      (node (ref "PX_DELAY") (pin "7") (pinfunction "TEST_7") (pintype "bidirectional"))
    )
    (net (code "243") (name "unconnected-(PX_DRIVE-TEST-Pad7)") (class "Default")
      (node (ref "PX_DRIVE") (pin "7") (pinfunction "TEST_7") (pintype "bidirectional"))
    )
    (net (code "244") (name "unconnected-(PX_HUMAN-TEST-Pad7)") (class "Default")
      (node (ref "PX_HUMAN") (pin "7") (pinfunction "TEST_7") (pintype "bidirectional"))
    )
    (net (code "245") (name "unconnected-(PX_LATCH-TEST-Pad7)") (class "Default")
      (node (ref "PX_LATCH") (pin "7") (pinfunction "TEST_7") (pintype "bidirectional"))
    )
    (net (code "246") (name "unconnected-(PX_ONOFF-TEST-Pad7)") (class "Default")
      (node (ref "PX_ONOFF") (pin "7") (pinfunction "TEST_7") (pintype "bidirectional"))
    )
    (net (code "247") (name "unconnected-(PX_PATTERN-TEST-Pad7)") (class "Default")
      (node (ref "PX_PATTERN") (pin "7") (pinfunction "TEST_7") (pintype "bidirectional"))
    )
    (net (code "248") (name "unconnected-(PX_PORTA-TEST-Pad7)") (class "Default")
      (node (ref "PX_PORTA") (pin "7") (pinfunction "TEST_7") (pintype "bidirectional"))
    )
    (net (code "249") (name "unconnected-(PX_RANGE-TEST-Pad7)") (class "Default")
      (node (ref "PX_RANGE") (pin "7") (pinfunction "TEST_7") (pintype "bidirectional"))
    )
    (net (code "250") (name "unconnected-(PX_RATE-TEST-Pad7)") (class "Default")
      (node (ref "PX_RATE") (pin "7") (pinfunction "TEST_7") (pintype "bidirectional"))
    )
    (net (code "251") (name "unconnected-(PX_REVERB-TEST-Pad7)") (class "Default")
      (node (ref "PX_REVERB") (pin "7") (pinfunction "TEST_7") (pintype "bidirectional"))
    )
    (net (code "252") (name "unconnected-(PX_SYNC-TEST-Pad7)") (class "Default")
      (node (ref "PX_SYNC") (pin "7") (pinfunction "TEST_7") (pintype "bidirectional"))
    )
    (net (code "253") (name "unconnected-(STLINK-Pad6)") (class "Default")
      (node (ref "STLINK") (pin "6") (pinfunction "6_6") (pintype "passive"))
    )
  )
)
